# hsa_stm32_board.net
KiCad netlist of a schematic drawn in EAGLE
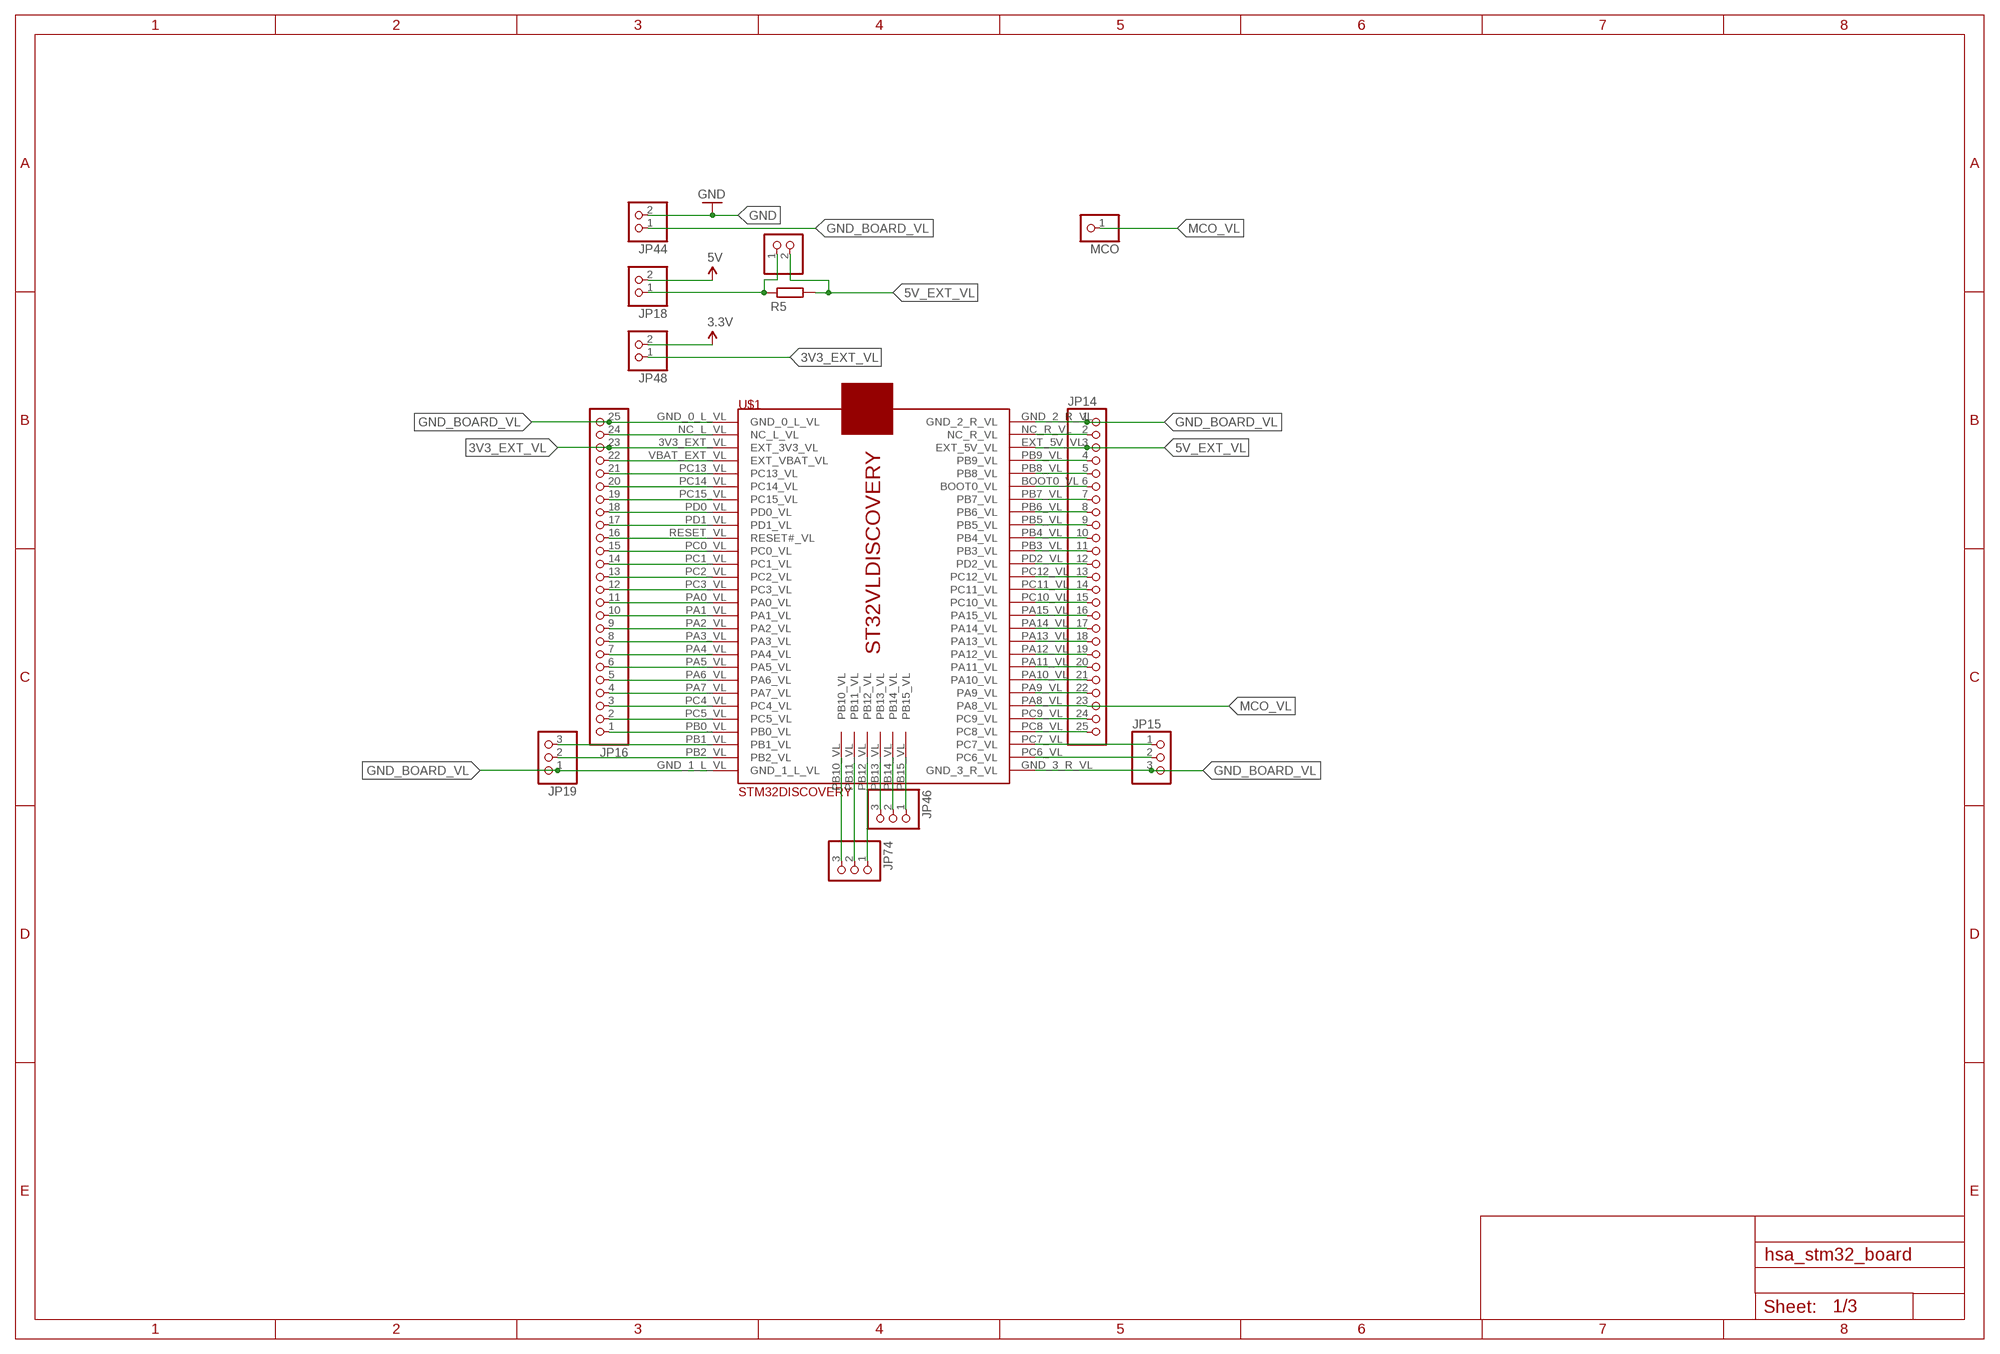
[diagram p0: schematic, sheet 1]
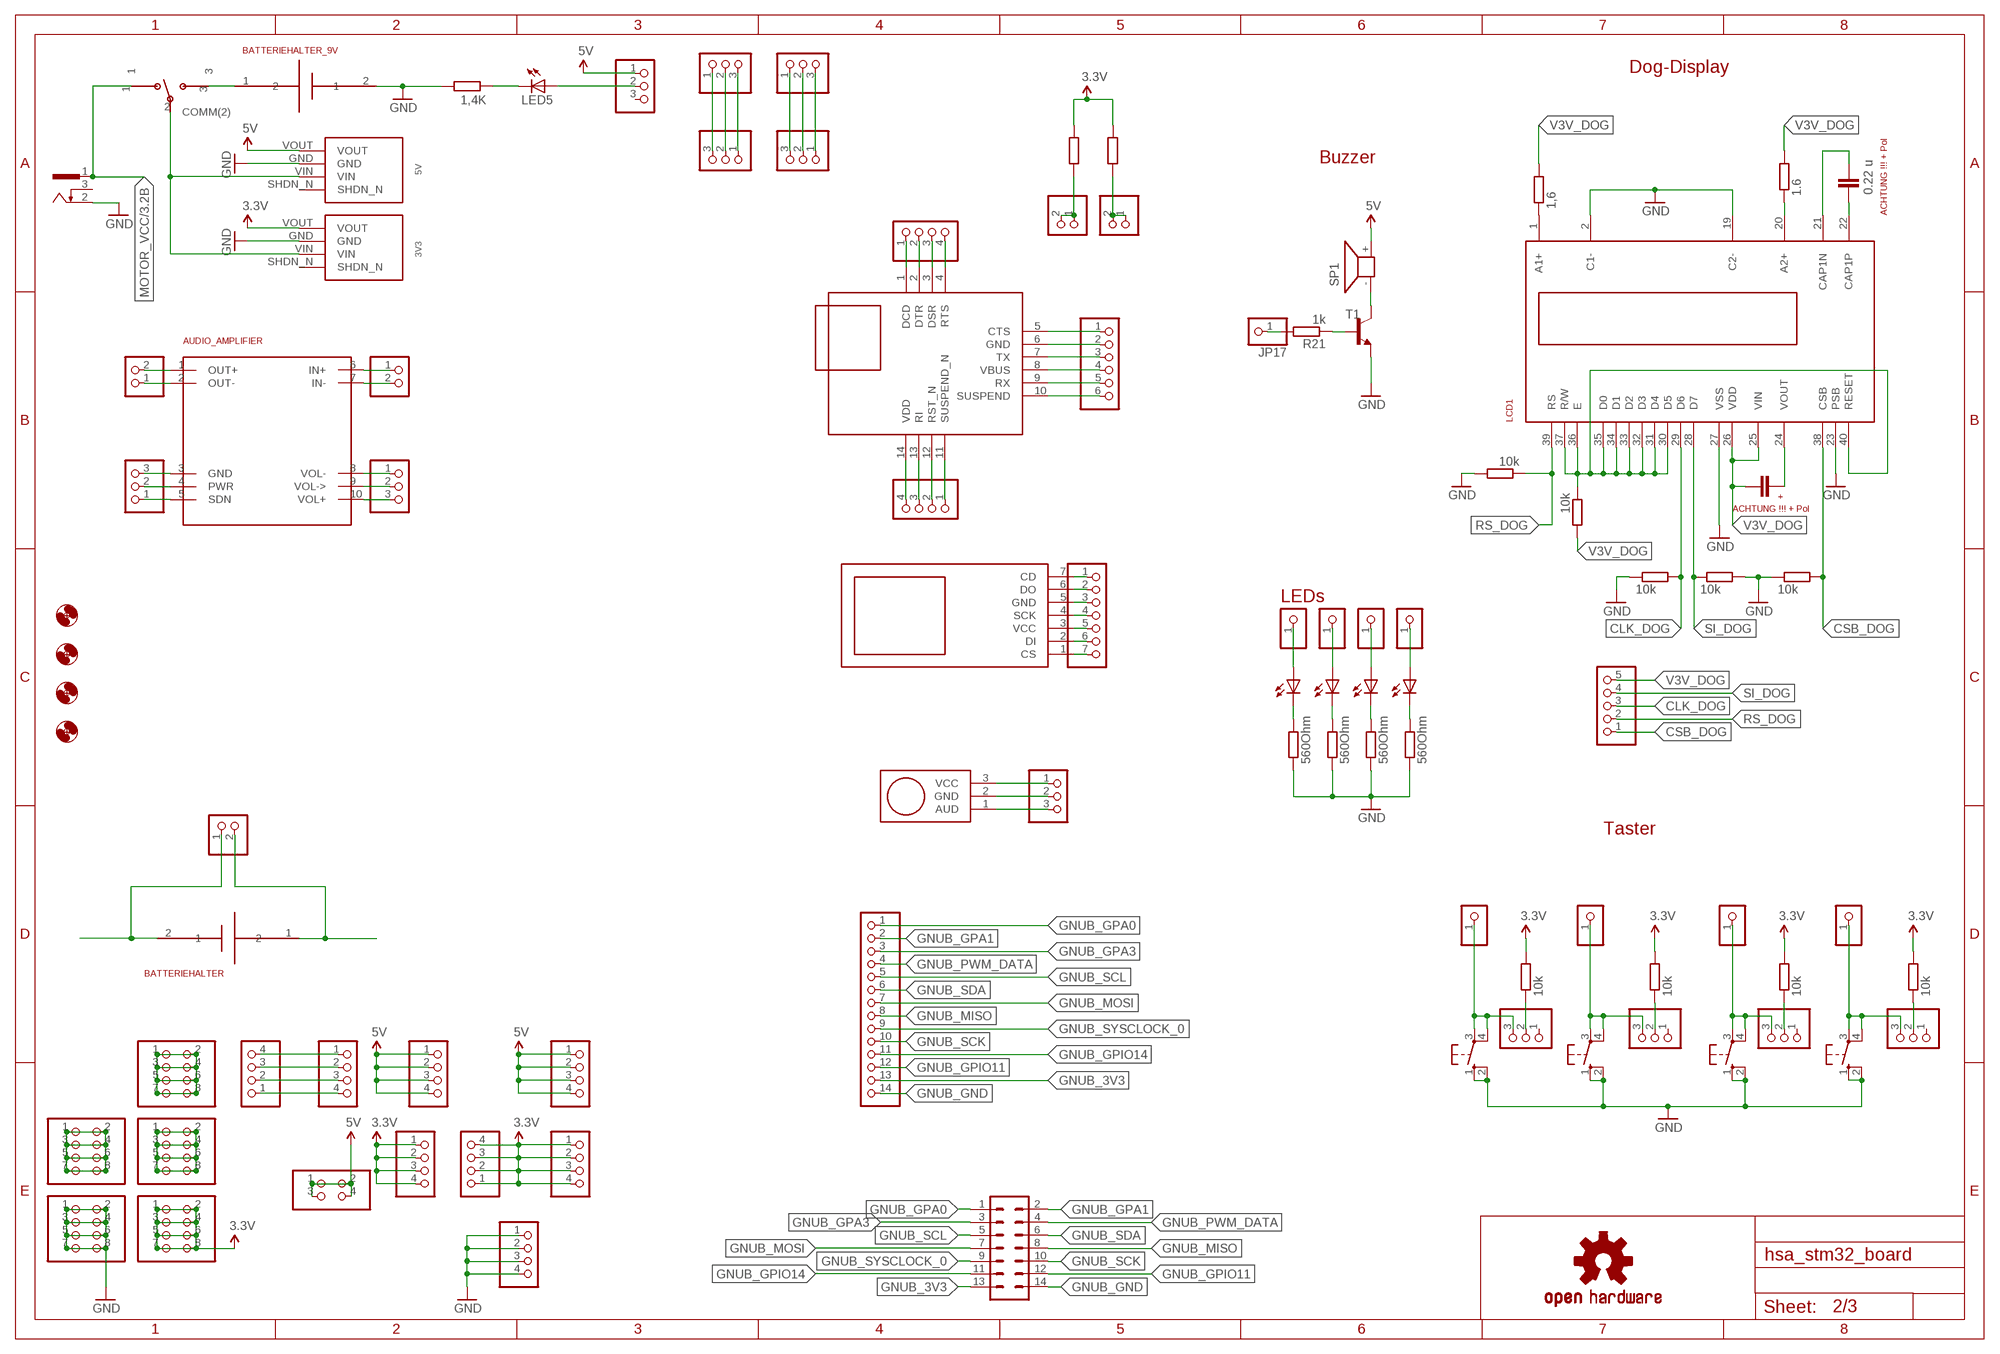
[diagram p1: schematic, sheet 2]
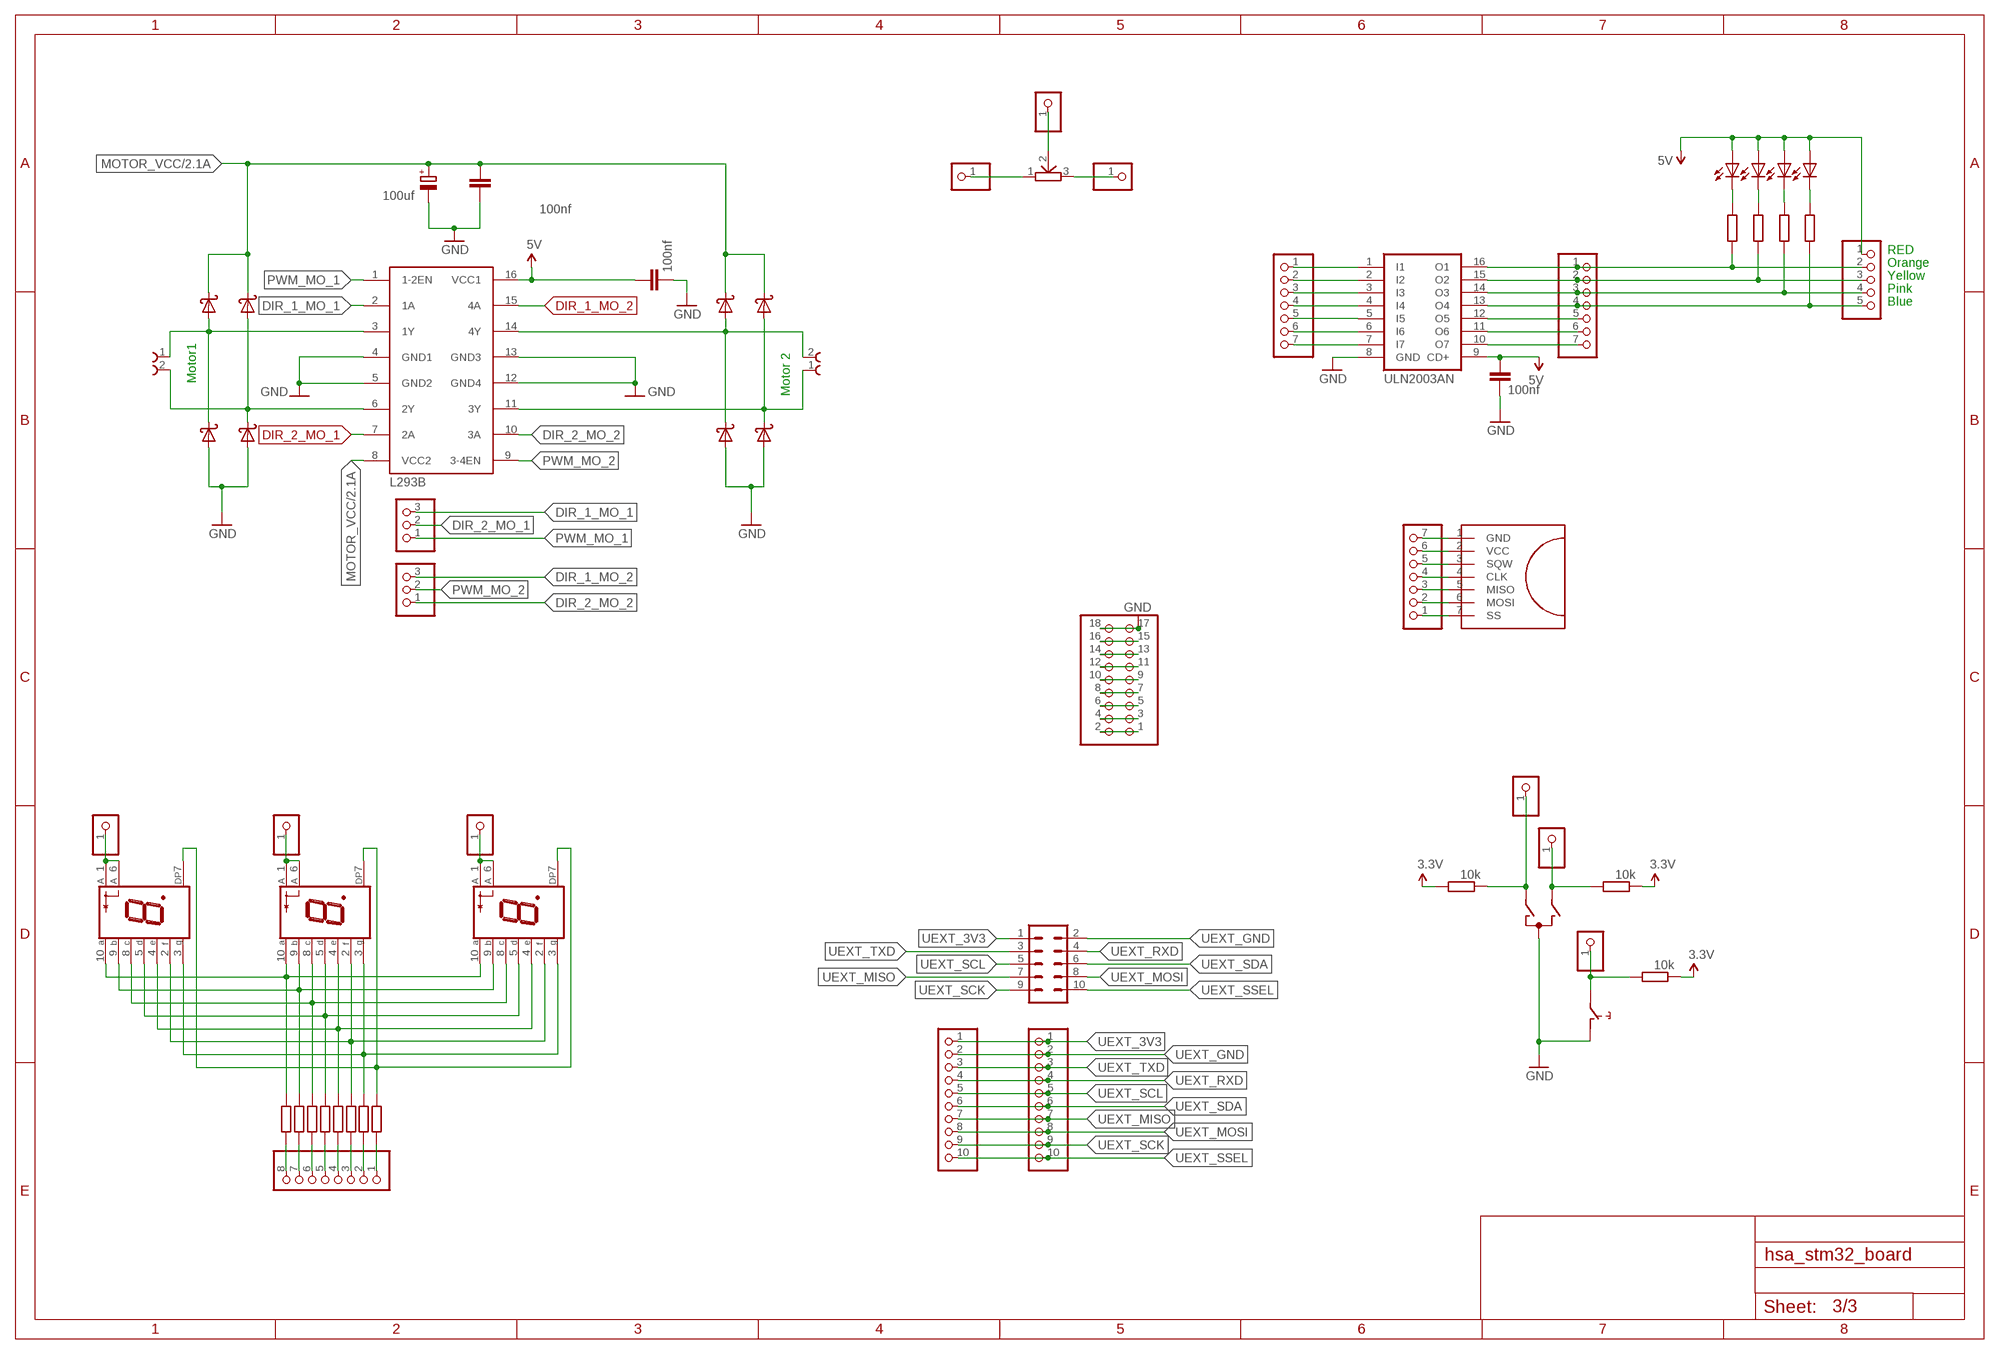
[diagram p2: schematic, sheet 3]

(export (version "E")
  (design (tool "Eeschema 10.0.6"))
  (components
    (comp (ref "JP14")
      (value "PINHD-1X25")
      (footprint "eagle-import:1X25")
      (libsource (lib "eagle-import") (part "PINHD-1X25"))
    )
    (comp (ref "JP15")
      (value "PINHD-1X3")
      (footprint "eagle-import:1X03")
      (libsource (lib "eagle-import") (part "PINHD-1X3"))
    )
    (comp (ref "JP16")
      (value "PINHD-1X25")
      (footprint "eagle-import:1X25")
      (libsource (lib "eagle-import") (part "PINHD-1X25"))
    )
    (comp (ref "JP18")
      (value "PINHD-1X2/90")
      (footprint "eagle-import:1X02_90")
      (libsource (lib "eagle-import") (part "PINHD-1X2/90"))
    )
    (comp (ref "JP19")
      (value "PINHD-1X3")
      (footprint "eagle-import:1X03")
      (libsource (lib "eagle-import") (part "PINHD-1X3"))
    )
    (comp (ref "JP44")
      (value "PINHD-1X2/90")
      (footprint "eagle-import:1X02_90")
      (libsource (lib "eagle-import") (part "PINHD-1X2/90"))
    )
    (comp (ref "JP46")
      (value "PINHD-1X3")
      (footprint "eagle-import:1X03")
      (libsource (lib "eagle-import") (part "PINHD-1X3"))
    )
    (comp (ref "JP48")
      (value "PINHD-1X2/90")
      (footprint "eagle-import:1X02_90")
      (libsource (lib "eagle-import") (part "PINHD-1X2/90"))
    )
    (comp (ref "JP74")
      (value "PINHD-1X3")
      (footprint "eagle-import:1X03")
      (libsource (lib "eagle-import") (part "PINHD-1X3"))
    )
    (comp (ref "JP75")
      (value "PINHD-1X2/90")
      (footprint "eagle-import:1X02_90")
      (libsource (lib "eagle-import") (part "PINHD-1X2/90"))
    )
    (comp (ref "MCO")
      (value "PINHD-1X1")
      (footprint "eagle-import:1X01")
      (libsource (lib "eagle-import") (part "PINHD-1X1"))
    )
    (comp (ref "R5")
      (value "R-EU_0207/10")
      (footprint "eagle-import:0207_10")
      (libsource (lib "eagle-import") (part "R-EU_0207/10"))
    )
    (comp (ref "U$1")
      (value "STM32DISCOVERY")
      (footprint "eagle-import:STM32DISCOVERY")
      (libsource (lib "eagle-import") (part "STM32DISCOVERY"))
    )
    (comp (ref "3V3")
      (value "VOLTAGE_REGULATOR")
      (footprint "eagle-import:VOL_REG")
      (libsource (lib "eagle-import") (part "VOLTAGE_REGULATOR"))
    )
    (comp (ref "5V")
      (value "VOLTAGE_REGULATOR")
      (footprint "eagle-import:VOL_REG")
      (libsource (lib "eagle-import") (part "VOLTAGE_REGULATOR"))
    )
    (comp (ref "C2")
      (value "0.22 u")
      (footprint "eagle-import:C025-040X050")
      (libsource (lib "eagle-import") (part "C-EU025-040X050"))
    )
    (comp (ref "C3")
      (value "1 u")
      (footprint "eagle-import:C025-040X050")
      (libsource (lib "eagle-import") (part "C-EU025-040X050"))
    )
    (comp (ref "H1")
      (value "MOUNT-HOLE2.8")
      (footprint "eagle-import:2,8")
      (libsource (lib "eagle-import") (part "MOUNT-HOLE2.8"))
    )
    (comp (ref "H2")
      (value "MOUNT-HOLE2.8")
      (footprint "eagle-import:2,8")
      (libsource (lib "eagle-import") (part "MOUNT-HOLE2.8"))
    )
    (comp (ref "H3")
      (value "MOUNT-HOLE2.8")
      (footprint "eagle-import:2,8")
      (libsource (lib "eagle-import") (part "MOUNT-HOLE2.8"))
    )
    (comp (ref "H4")
      (value "MOUNT-HOLE2.8")
      (footprint "eagle-import:2,8")
      (libsource (lib "eagle-import") (part "MOUNT-HOLE2.8"))
    )
    (comp (ref "JP1")
      (value "PINHD-1X5")
      (footprint "eagle-import:1X05")
      (libsource (lib "eagle-import") (part "PINHD-1X5"))
    )
    (comp (ref "JP4")
      (value "PINHD-1X3")
      (footprint "eagle-import:1X03")
      (libsource (lib "eagle-import") (part "PINHD-1X3"))
    )
    (comp (ref "JP5")
      (value "PINHD-1X1")
      (footprint "eagle-import:1X01")
      (libsource (lib "eagle-import") (part "PINHD-1X1"))
    )
    (comp (ref "JP6")
      (value "PINHD-1X1")
      (footprint "eagle-import:1X01")
      (libsource (lib "eagle-import") (part "PINHD-1X1"))
    )
    (comp (ref "JP7")
      (value "PINHD-1X1")
      (footprint "eagle-import:1X01")
      (libsource (lib "eagle-import") (part "PINHD-1X1"))
    )
    (comp (ref "JP8")
      (value "PINHD-1X1")
      (footprint "eagle-import:1X01")
      (libsource (lib "eagle-import") (part "PINHD-1X1"))
    )
    (comp (ref "JP9")
      (value "PINHD-1X1")
      (footprint "eagle-import:1X01")
      (libsource (lib "eagle-import") (part "PINHD-1X1"))
    )
    (comp (ref "JP10")
      (value "PINHD-1X1")
      (footprint "eagle-import:1X01")
      (libsource (lib "eagle-import") (part "PINHD-1X1"))
    )
    (comp (ref "JP11")
      (value "PINHD-1X1")
      (footprint "eagle-import:1X01")
      (libsource (lib "eagle-import") (part "PINHD-1X1"))
    )
    (comp (ref "JP12")
      (value "PINHD-1X1")
      (footprint "eagle-import:1X01")
      (libsource (lib "eagle-import") (part "PINHD-1X1"))
    )
    (comp (ref "JP17")
      (value "PINHD-1X1")
      (footprint "eagle-import:1X01")
      (libsource (lib "eagle-import") (part "PINHD-1X1"))
    )
    (comp (ref "JP24")
      (value "PINHD-1X4")
      (footprint "eagle-import:1X04")
      (libsource (lib "eagle-import") (part "PINHD-1X4"))
    )
    (comp (ref "JP27")
      (value "PINHD-1X4/90")
      (footprint "eagle-import:1X04_90")
      (libsource (lib "eagle-import") (part "PINHD-1X4/90"))
    )
    (comp (ref "JP28")
      (value "PINHD-1X4")
      (footprint "eagle-import:1X04")
      (libsource (lib "eagle-import") (part "PINHD-1X4"))
    )
    (comp (ref "JP29")
      (value "PINHD-1X4")
      (footprint "eagle-import:1X04")
      (libsource (lib "eagle-import") (part "PINHD-1X4"))
    )
    (comp (ref "JP30")
      (value "PINHD-1X3")
      (footprint "eagle-import:1X03")
      (libsource (lib "eagle-import") (part "PINHD-1X3"))
    )
    (comp (ref "JP31")
      (value "PINHD-1X2")
      (footprint "eagle-import:1X02")
      (libsource (lib "eagle-import") (part "PINHD-1X2"))
    )
    (comp (ref "JP32")
      (value "PINHD-1X2")
      (footprint "eagle-import:1X02")
      (libsource (lib "eagle-import") (part "PINHD-1X2"))
    )
    (comp (ref "JP33")
      (value "PINHD-1X3")
      (footprint "eagle-import:1X03")
      (libsource (lib "eagle-import") (part "PINHD-1X3"))
    )
    (comp (ref "JP34")
      (value "PINHD-1X3")
      (footprint "eagle-import:1X03")
      (libsource (lib "eagle-import") (part "PINHD-1X3"))
    )
    (comp (ref "JP36")
      (value "PINHD-1X4")
      (footprint "eagle-import:1X04")
      (libsource (lib "eagle-import") (part "PINHD-1X4"))
    )
    (comp (ref "JP37")
      (value "PINHD-1X4")
      (footprint "eagle-import:1X04")
      (libsource (lib "eagle-import") (part "PINHD-1X4"))
    )
    (comp (ref "JP38")
      (value "PINHD-1X6")
      (footprint "eagle-import:1X06")
      (libsource (lib "eagle-import") (part "PINHD-1X6"))
    )
    (comp (ref "JP39")
      (value "PINHD-1X7")
      (footprint "eagle-import:1X07")
      (libsource (lib "eagle-import") (part "PINHD-1X7"))
    )
    (comp (ref "JP40")
      (value "PINHD-1X4")
      (footprint "eagle-import:1X04")
      (libsource (lib "eagle-import") (part "PINHD-1X4"))
    )
    (comp (ref "JP41")
      (value "PINHD-1X4")
      (footprint "eagle-import:1X04")
      (libsource (lib "eagle-import") (part "PINHD-1X4"))
    )
    (comp (ref "JP42")
      (value "PINHD-1X4")
      (footprint "eagle-import:1X04")
      (libsource (lib "eagle-import") (part "PINHD-1X4"))
    )
    (comp (ref "JP43")
      (value "PINHD-1X2")
      (footprint "eagle-import:1X02")
      (libsource (lib "eagle-import") (part "PINHD-1X2"))
    )
    (comp (ref "JP45")
      (value "PINHD-2X4")
      (footprint "eagle-import:2X04")
      (libsource (lib "eagle-import") (part "PINHD-2X4"))
    )
    (comp (ref "JP47")
      (value "PINHD-1X4")
      (footprint "eagle-import:1X04")
      (libsource (lib "eagle-import") (part "PINHD-1X4"))
    )
    (comp (ref "JP49")
      (value "PINHD-1X3/90")
      (footprint "eagle-import:1X03_90")
      (libsource (lib "eagle-import") (part "PINHD-1X3/90"))
    )
    (comp (ref "JP50")
      (value "PINHD-1X3")
      (footprint "eagle-import:1X03")
      (libsource (lib "eagle-import") (part "PINHD-1X3"))
    )
    (comp (ref "JP51")
      (value "PINHD-1X3/90")
      (footprint "eagle-import:1X03_90")
      (libsource (lib "eagle-import") (part "PINHD-1X3/90"))
    )
    (comp (ref "JP52")
      (value "PINHD-1X3")
      (footprint "eagle-import:1X03")
      (libsource (lib "eagle-import") (part "PINHD-1X3"))
    )
    (comp (ref "JP59")
      (value "PINHD-1X3")
      (footprint "eagle-import:1X03")
      (libsource (lib "eagle-import") (part "PINHD-1X3"))
    )
    (comp (ref "JP60")
      (value "PINHD-1X3")
      (footprint "eagle-import:1X03")
      (libsource (lib "eagle-import") (part "PINHD-1X3"))
    )
    (comp (ref "JP61")
      (value "PINHD-1X3")
      (footprint "eagle-import:1X03")
      (libsource (lib "eagle-import") (part "PINHD-1X3"))
    )
    (comp (ref "JP62")
      (value "PINHD-1X3")
      (footprint "eagle-import:1X03")
      (libsource (lib "eagle-import") (part "PINHD-1X3"))
    )
    (comp (ref "JP64")
      (value "PINHD-1X14")
      (footprint "eagle-import:1X14")
      (libsource (lib "eagle-import") (part "PINHD-1X14"))
    )
    (comp (ref "JP65")
      (value "PINHD-1X2")
      (footprint "eagle-import:1X02")
      (libsource (lib "eagle-import") (part "PINHD-1X2"))
    )
    (comp (ref "JP66")
      (value "PINHD-1X2")
      (footprint "eagle-import:1X02")
      (libsource (lib "eagle-import") (part "PINHD-1X2"))
    )
    (comp (ref "JP67")
      (value "PINHD-2X4")
      (footprint "eagle-import:2X04")
      (libsource (lib "eagle-import") (part "PINHD-2X4"))
    )
    (comp (ref "JP68")
      (value "PINHD-2X4")
      (footprint "eagle-import:2X04")
      (libsource (lib "eagle-import") (part "PINHD-2X4"))
    )
    (comp (ref "JP69")
      (value "PINHD-2X4")
      (footprint "eagle-import:2X04")
      (libsource (lib "eagle-import") (part "PINHD-2X4"))
    )
    (comp (ref "JP70")
      (value "PINHD-2X4")
      (footprint "eagle-import:2X04")
      (libsource (lib "eagle-import") (part "PINHD-2X4"))
    )
    (comp (ref "JP71")
      (value "PINHD-2X2")
      (footprint "eagle-import:2X02")
      (libsource (lib "eagle-import") (part "PINHD-2X2"))
    )
    (comp (ref "LCD1")
      (value "ZEITERFASSUNG_-OPTO_DOGM")
      (footprint "eagle-import:ZEITERFASSUNG_-OPTO_DOGM")
      (libsource (lib "eagle-import") (part "ZEITERFASSUNG_-OPTO_DOGM"))
    )
    (comp (ref "LED1")
      (value "LED5MM")
      (footprint "eagle-import:LED5MM")
      (libsource (lib "eagle-import") (part "LED5MM"))
    )
    (comp (ref "LED2")
      (value "LED5MM")
      (footprint "eagle-import:LED5MM")
      (libsource (lib "eagle-import") (part "LED5MM"))
    )
    (comp (ref "LED3")
      (value "LED5MM")
      (footprint "eagle-import:LED5MM")
      (libsource (lib "eagle-import") (part "LED5MM"))
    )
    (comp (ref "LED4")
      (value "LED5MM")
      (footprint "eagle-import:LED5MM")
      (libsource (lib "eagle-import") (part "LED5MM"))
    )
    (comp (ref "LED5")
      (value "LED5MM")
      (footprint "eagle-import:LED5MM")
      (libsource (lib "eagle-import") (part "LED5MM"))
    )
    (comp (ref "LOGO1")
      (value "OSHW-LOGOL")
      (footprint "eagle-import:OSHW-LOGO-L")
      (libsource (lib "eagle-import") (part "OSHW-LOGOL"))
    )
    (comp (ref "R1")
      (value "560Ohm")
      (footprint "eagle-import:0207_10")
      (libsource (lib "eagle-import") (part "R-EU_0207/10"))
    )
    (comp (ref "R2")
      (value "560Ohm")
      (footprint "eagle-import:0207_10")
      (libsource (lib "eagle-import") (part "R-EU_0207/10"))
    )
    (comp (ref "R3")
      (value "560Ohm")
      (footprint "eagle-import:0207_10")
      (libsource (lib "eagle-import") (part "R-EU_0207/10"))
    )
    (comp (ref "R4")
      (value "560Ohm")
      (footprint "eagle-import:0207_10")
      (libsource (lib "eagle-import") (part "R-EU_0207/10"))
    )
    (comp (ref "R6")
      (value "1,4K")
      (footprint "eagle-import:0207_10")
      (libsource (lib "eagle-import") (part "R-EU_0207/10"))
    )
    (comp (ref "R7")
      (value "1.6")
      (footprint "eagle-import:0207_10")
      (libsource (lib "eagle-import") (part "R-EU_0207/10"))
    )
    (comp (ref "R8")
      (value "1,6")
      (footprint "eagle-import:0207_10")
      (libsource (lib "eagle-import") (part "R-EU_0207/10"))
    )
    (comp (ref "R9")
      (value "10k")
      (footprint "eagle-import:0207_10")
      (libsource (lib "eagle-import") (part "R-EU_0207/10"))
    )
    (comp (ref "R10")
      (value "10k")
      (footprint "eagle-import:0207_10")
      (libsource (lib "eagle-import") (part "R-EU_0207/10"))
    )
    (comp (ref "R11")
      (value "10k")
      (footprint "eagle-import:0207_10")
      (libsource (lib "eagle-import") (part "R-EU_0207/10"))
    )
    (comp (ref "R12")
      (value "10k")
      (footprint "eagle-import:0207_10")
      (libsource (lib "eagle-import") (part "R-EU_0207/10"))
    )
    (comp (ref "R13")
      (value "10k")
      (footprint "eagle-import:0207_10")
      (libsource (lib "eagle-import") (part "R-EU_0207/10"))
    )
    (comp (ref "R14")
      (value "10k")
      (footprint "eagle-import:0207_10")
      (libsource (lib "eagle-import") (part "R-EU_0207/10"))
    )
    (comp (ref "R15")
      (value "10k")
      (footprint "eagle-import:0207_10")
      (libsource (lib "eagle-import") (part "R-EU_0207/10"))
    )
    (comp (ref "R16")
      (value "10k")
      (footprint "eagle-import:0207_10")
      (libsource (lib "eagle-import") (part "R-EU_0207/10"))
    )
    (comp (ref "R17")
      (value "10k")
      (footprint "eagle-import:0207_10")
      (libsource (lib "eagle-import") (part "R-EU_0207/10"))
    )
    (comp (ref "R21")
      (value "1k")
      (footprint "eagle-import:0207_10")
      (libsource (lib "eagle-import") (part "R-EU_0207/10"))
    )
    (comp (ref "R22")
      (value "R-EU_0207/10")
      (footprint "eagle-import:0207_10")
      (libsource (lib "eagle-import") (part "R-EU_0207/10"))
    )
    (comp (ref "R23")
      (value "R-EU_0207/10")
      (footprint "eagle-import:0207_10")
      (libsource (lib "eagle-import") (part "R-EU_0207/10"))
    )
    (comp (ref "S1")
      (value "CPU-K_MODULE_REV3.0_SWITCH-OMRON_10-XX")
      (footprint "eagle-import:CPU-K_MODULE_REV3.0_SWITCH-OMRON_B3F-10XX")
      (libsource (lib "eagle-import") (part "CPU-K_MODULE_REV3.0_SWITCH-OMRON_10-XX"))
    )
    (comp (ref "S2")
      (value "CPU-K_MODULE_REV3.0_SWITCH-OMRON_10-XX")
      (footprint "eagle-import:CPU-K_MODULE_REV3.0_SWITCH-OMRON_B3F-10XX")
      (libsource (lib "eagle-import") (part "CPU-K_MODULE_REV3.0_SWITCH-OMRON_10-XX"))
    )
    (comp (ref "S3")
      (value "CPU-K_MODULE_REV3.0_SWITCH-OMRON_10-XX")
      (footprint "eagle-import:CPU-K_MODULE_REV3.0_SWITCH-OMRON_B3F-10XX")
      (libsource (lib "eagle-import") (part "CPU-K_MODULE_REV3.0_SWITCH-OMRON_10-XX"))
    )
    (comp (ref "S4")
      (value "CPU-K_MODULE_REV3.0_SWITCH-OMRON_10-XX")
      (footprint "eagle-import:CPU-K_MODULE_REV3.0_SWITCH-OMRON_B3F-10XX")
      (libsource (lib "eagle-import") (part "CPU-K_MODULE_REV3.0_SWITCH-OMRON_10-XX"))
    )
    (comp (ref "SP1")
      (value "BUZZER_F/PMX04")
      (footprint "eagle-import:BUZZER_F_PMX04A")
      (libsource (lib "eagle-import") (part "BUZZER_F/PMX04"))
    )
    (comp (ref "SV3")
      (value "ML14")
      (footprint "eagle-import:ML14")
      (libsource (lib "eagle-import") (part "ML14"))
    )
    (comp (ref "T1")
      (value "TRANSISTOR_BC337")
      (footprint "eagle-import:TRANSISTOR_TO92")
      (libsource (lib "eagle-import") (part "TRANSISTOR_BC337"))
    )
    (comp (ref "U$2")
      (value "USB_TO_SERIAL_ADAPTER")
      (footprint "eagle-import:USB_TO_SERIAL")
      (libsource (lib "eagle-import") (part "USB_TO_SERIAL_ADAPTER"))
    )
    (comp (ref "U$4")
      (value "KIPPSCHALTER(EIN,AUS,EIN)")
      (footprint "eagle-import:KIPPSCHALTER")
      (libsource (lib "eagle-import") (part "KIPPSCHALTER(EIN,AUS,EIN)"))
    )
    (comp (ref "U$5")
      (value "MIC")
      (footprint "eagle-import:MIC")
      (libsource (lib "eagle-import") (part "MIC"))
    )
    (comp (ref "U$6")
      (value "BATTERIEHALTER")
      (footprint "eagle-import:BH_KZH_20")
      (libsource (lib "eagle-import") (part "BATTERIEHALTER"))
    )
    (comp (ref "U$7")
      (value "BATTERIEHALTER_9V")
      (footprint "eagle-import:BATTERIEHALTER_9V")
      (libsource (lib "eagle-import") (part "BATTERIEHALTER_9V"))
    )
    (comp (ref "U$9")
      (value "AUDIO_AMPLIFIER")
      (footprint "eagle-import:AUDIO_AMPLIFIER")
      (libsource (lib "eagle-import") (part "AUDIO_AMPLIFIER"))
    )
    (comp (ref "U$12")
      (value "MICRO_SD_HALTER")
      (footprint "eagle-import:MIKRO_SD_HALTER")
      (libsource (lib "eagle-import") (part "MICRO_SD_HALTER"))
    )
    (comp (ref "X1")
      (value "733980-62")
      (footprint "eagle-import:733980-62")
      (libsource (lib "eagle-import") (part "73398?0-62"))
    )
    (comp (ref "C4")
      (value "100nf")
      (footprint "eagle-import:RCL_C025-040X050")
      (libsource (lib "eagle-import") (part "RCL_C-EU025-040X050"))
    )
    (comp (ref "C5")
      (value "100nf")
      (footprint "eagle-import:RCL_C025-040X050")
      (libsource (lib "eagle-import") (part "RCL_C-EU025-040X050"))
    )
    (comp (ref "C6")
      (value "100nf")
      (footprint "eagle-import:RCL_C025-040X050")
      (libsource (lib "eagle-import") (part "RCL_C-EU025-040X050"))
    )
    (comp (ref "C7")
      (value "100uf")
      (footprint "eagle-import:RCL_E2,5-6")
      (libsource (lib "eagle-import") (part "RCL_CPOL-EUE2.5-6"))
    )
    (comp (ref "D1")
      (value "1N5819")
      (footprint "eagle-import:DO41-10")
      (libsource (lib "eagle-import") (part "1N5819"))
    )
    (comp (ref "D2")
      (value "1N5819")
      (footprint "eagle-import:DO41-10")
      (libsource (lib "eagle-import") (part "1N5819"))
    )
    (comp (ref "D3")
      (value "1N5819")
      (footprint "eagle-import:DO41-10")
      (libsource (lib "eagle-import") (part "1N5819"))
    )
    (comp (ref "D4")
      (value "1N5819")
      (footprint "eagle-import:DO41-10")
      (libsource (lib "eagle-import") (part "1N5819"))
    )
    (comp (ref "D5")
      (value "1N5819")
      (footprint "eagle-import:DO41-10")
      (libsource (lib "eagle-import") (part "1N5819"))
    )
    (comp (ref "D6")
      (value "1N5819")
      (footprint "eagle-import:DO41-10")
      (libsource (lib "eagle-import") (part "1N5819"))
    )
    (comp (ref "D7")
      (value "1N5819")
      (footprint "eagle-import:DO41-10")
      (libsource (lib "eagle-import") (part "1N5819"))
    )
    (comp (ref "D8")
      (value "1N5819")
      (footprint "eagle-import:DO41-10")
      (libsource (lib "eagle-import") (part "1N5819"))
    )
    (comp (ref "IC1")
      (value "ULN2003AN")
      (footprint "eagle-import:DIL16")
      (libsource (lib "eagle-import") (part "ULN2003AN"))
    )
    (comp (ref "IC2")
      (value "L293D")
      (footprint "eagle-import:DIL16")
      (libsource (lib "eagle-import") (part "L293D"))
    )
    (comp (ref "JP2")
      (value "PINHD-1X1")
      (footprint "eagle-import:1X01")
      (libsource (lib "eagle-import") (part "PINHD-1X1"))
    )
    (comp (ref "JP3")
      (value "PINHD-1X1")
      (footprint "eagle-import:1X01")
      (libsource (lib "eagle-import") (part "PINHD-1X1"))
    )
    (comp (ref "JP13")
      (value "PINHD-1X1")
      (footprint "eagle-import:1X01")
      (libsource (lib "eagle-import") (part "PINHD-1X1"))
    )
    (comp (ref "JP20")
      (value "PINHD-1X10")
      (footprint "eagle-import:1X10")
      (libsource (lib "eagle-import") (part "PINHD-1X10"))
    )
    (comp (ref "JP21")
      (value "PINHD-1X7")
      (footprint "eagle-import:1X07")
      (libsource (lib "eagle-import") (part "PINHD-1X7"))
    )
    (comp (ref "JP22")
      (value "PINHD-1X8")
      (footprint "eagle-import:1X08")
      (libsource (lib "eagle-import") (part "PINHD-1X8"))
    )
    (comp (ref "JP23")
      (value "PINHD-1X1")
      (footprint "eagle-import:1X01")
      (libsource (lib "eagle-import") (part "PINHD-1X1"))
    )
    (comp (ref "JP25")
      (value "PINHD-1X5/90")
      (footprint "eagle-import:1X05_90")
      (libsource (lib "eagle-import") (part "PINHD-1X5/90"))
    )
    (comp (ref "JP26")
      (value "PINHD-1X7")
      (footprint "eagle-import:1X07")
      (libsource (lib "eagle-import") (part "PINHD-1X7"))
    )
    (comp (ref "JP35")
      (value "PINHD-1X7")
      (footprint "eagle-import:1X07")
      (libsource (lib "eagle-import") (part "PINHD-1X7"))
    )
    (comp (ref "JP53")
      (value "PINHD-1X1")
      (footprint "eagle-import:1X01")
      (libsource (lib "eagle-import") (part "PINHD-1X1"))
    )
    (comp (ref "JP54")
      (value "PINHD-1X1")
      (footprint "eagle-import:1X01")
      (libsource (lib "eagle-import") (part "PINHD-1X1"))
    )
    (comp (ref "JP55")
      (value "PINHD-1X1")
      (footprint "eagle-import:1X01")
      (libsource (lib "eagle-import") (part "PINHD-1X1"))
    )
    (comp (ref "JP56")
      (value "PINHD-2X9")
      (footprint "eagle-import:2X09")
      (libsource (lib "eagle-import") (part "PINHD-2X9"))
    )
    (comp (ref "JP57")
      (value "PINHD-1X3")
      (footprint "eagle-import:1X03")
      (libsource (lib "eagle-import") (part "PINHD-1X3"))
    )
    (comp (ref "JP58")
      (value "PINHD-1X3")
      (footprint "eagle-import:1X03")
      (libsource (lib "eagle-import") (part "PINHD-1X3"))
    )
    (comp (ref "JP63")
      (value "PINHD-1X10")
      (footprint "eagle-import:1X10")
      (libsource (lib "eagle-import") (part "PINHD-1X10"))
    )
    (comp (ref "JP72")
      (value "PINHD-1X1")
      (footprint "eagle-import:1X01")
      (libsource (lib "eagle-import") (part "PINHD-1X1"))
    )
    (comp (ref "JP73")
      (value "PINHD-1X1")
      (footprint "eagle-import:1X01")
      (libsource (lib "eagle-import") (part "PINHD-1X1"))
    )
    (comp (ref "K1")
      (value "691210910002")
      (footprint "eagle-import:691210910002")
      (libsource (lib "eagle-import") (part "691210910002"))
    )
    (comp (ref "K2")
      (value "691210910002")
      (footprint "eagle-import:691210910002")
      (libsource (lib "eagle-import") (part "691210910002"))
    )
    (comp (ref "LED6")
      (value "LA-401MD")
      (footprint "eagle-import:LA-401")
      (libsource (lib "eagle-import") (part "LA-401DM"))
    )
    (comp (ref "LED7")
      (value "LA-401MD")
      (footprint "eagle-import:LA-401")
      (libsource (lib "eagle-import") (part "LA-401DM"))
    )
    (comp (ref "LED8")
      (value "LA-401MD")
      (footprint "eagle-import:LA-401")
      (libsource (lib "eagle-import") (part "LA-401DM"))
    )
    (comp (ref "LED9")
      (value "LED3MM")
      (footprint "eagle-import:LED3MM")
      (libsource (lib "eagle-import") (part "LED3MM"))
    )
    (comp (ref "LED10")
      (value "LED3MM")
      (footprint "eagle-import:LED3MM")
      (libsource (lib "eagle-import") (part "LED3MM"))
    )
    (comp (ref "LED11")
      (value "LED3MM")
      (footprint "eagle-import:LED3MM")
      (libsource (lib "eagle-import") (part "LED3MM"))
    )
    (comp (ref "LED12")
      (value "LED3MM")
      (footprint "eagle-import:LED3MM")
      (libsource (lib "eagle-import") (part "LED3MM"))
    )
    (comp (ref "R18")
      (value "10k")
      (footprint "eagle-import:0207_10")
      (libsource (lib "eagle-import") (part "R-EU_0207/10"))
    )
    (comp (ref "R19")
      (value "10k")
      (footprint "eagle-import:0207_10")
      (libsource (lib "eagle-import") (part "R-EU_0207/10"))
    )
    (comp (ref "R20")
      (value "10k")
      (footprint "eagle-import:0207_10")
      (libsource (lib "eagle-import") (part "R-EU_0207/10"))
    )
    (comp (ref "R24")
      (value "R-EU_0207/10")
      (footprint "eagle-import:0207_10")
      (libsource (lib "eagle-import") (part "R-EU_0207/10"))
    )
    (comp (ref "R25")
      (value "R-EU_0207/10")
      (footprint "eagle-import:0207_10")
      (libsource (lib "eagle-import") (part "R-EU_0207/10"))
    )
    (comp (ref "R26")
      (value "R-EU_0207/10")
      (footprint "eagle-import:0207_10")
      (libsource (lib "eagle-import") (part "R-EU_0207/10"))
    )
    (comp (ref "R27")
      (value "R-EU_0207/10")
      (footprint "eagle-import:0207_10")
      (libsource (lib "eagle-import") (part "R-EU_0207/10"))
    )
    (comp (ref "R28")
      (value "R-EU_0207/10")
      (footprint "eagle-import:0207_10")
      (libsource (lib "eagle-import") (part "R-EU_0207/10"))
    )
    (comp (ref "R29")
      (value "R-EU_0207/10")
      (footprint "eagle-import:0207_10")
      (libsource (lib "eagle-import") (part "R-EU_0207/10"))
    )
    (comp (ref "R30")
      (value "R-EU_0207/10")
      (footprint "eagle-import:0207_10")
      (libsource (lib "eagle-import") (part "R-EU_0207/10"))
    )
    (comp (ref "R31")
      (value "R-EU_0207/10")
      (footprint "eagle-import:0207_10")
      (libsource (lib "eagle-import") (part "R-EU_0207/10"))
    )
    (comp (ref "R32")
      (value "R-EU_0207/10")
      (footprint "eagle-import:0207_10")
      (libsource (lib "eagle-import") (part "R-EU_0207/10"))
    )
    (comp (ref "R33")
      (value "R-EU_0207/10")
      (footprint "eagle-import:0207_10")
      (libsource (lib "eagle-import") (part "R-EU_0207/10"))
    )
    (comp (ref "R34")
      (value "R-EU_0207/10")
      (footprint "eagle-import:0207_10")
      (libsource (lib "eagle-import") (part "R-EU_0207/10"))
    )
    (comp (ref "R35")
      (value "R-EU_0207/10")
      (footprint "eagle-import:0207_10")
      (libsource (lib "eagle-import") (part "R-EU_0207/10"))
    )
    (comp (ref "SV2")
      (value "CON-HARTING-ML_ML10")
      (footprint "eagle-import:CON-HARTING-ML_ML10")
      (libsource (lib "eagle-import") (part "CON-HARTING-ML_ML10"))
    )
    (comp (ref "SW1")
      (value "EC12E_SW")
      (footprint "eagle-import:ALPS_EC12E_SW")
      (fields (field (name "MPN") "EC12E2424407"))
      (libsource (lib "eagle-import") (part "EC12E_SW"))
    )
    (comp (ref "U$10")
      (value "RTC")
      (footprint "eagle-import:RTC")
      (libsource (lib "eagle-import") (part "RTC"))
    )
    (comp (ref "U$17")
      (value "THUMBWHEEL_POTI")
      (footprint "eagle-import:THUMBWHEEL_POTI")
      (libsource (lib "eagle-import") (part "THUMBWHEEL_POTI"))
    )
  )
  (nets
    (net (code "1") (name "3.3V") (class "Default")
      (node (ref "3V3") (pin "VOUT") (pinfunction "VOUT_VOUT") (pintype "bidirectional"))
      (node (ref "JP29") (pin "1") (pinfunction "1_1") (pintype "passive"))
      (node (ref "JP29") (pin "2") (pinfunction "2_2") (pintype "passive"))
      (node (ref "JP29") (pin "3") (pinfunction "3_3") (pintype "passive"))
      (node (ref "JP29") (pin "4") (pinfunction "4_4") (pintype "passive"))
      (node (ref "JP41") (pin "1") (pinfunction "1_1") (pintype "passive"))
      (node (ref "JP41") (pin "2") (pinfunction "2_2") (pintype "passive"))
      (node (ref "JP41") (pin "3") (pinfunction "3_3") (pintype "passive"))
      (node (ref "JP41") (pin "4") (pinfunction "4_4") (pintype "passive"))
      (node (ref "JP47") (pin "1") (pinfunction "1_1") (pintype "passive"))
      (node (ref "JP47") (pin "2") (pinfunction "2_2") (pintype "passive"))
      (node (ref "JP47") (pin "3") (pinfunction "3_3") (pintype "passive"))
      (node (ref "JP47") (pin "4") (pinfunction "4_4") (pintype "passive"))
      (node (ref "JP48") (pin "2") (pinfunction "2_2") (pintype "passive"))
      (node (ref "JP70") (pin "1") (pinfunction "1_1") (pintype "passive"))
      (node (ref "JP70") (pin "2") (pinfunction "2_2") (pintype "passive"))
      (node (ref "JP70") (pin "3") (pinfunction "3_3") (pintype "passive"))
      (node (ref "JP70") (pin "4") (pinfunction "4_4") (pintype "passive"))
      (node (ref "JP70") (pin "5") (pinfunction "5_5") (pintype "passive"))
      (node (ref "JP70") (pin "6") (pinfunction "6_6") (pintype "passive"))
      (node (ref "JP70") (pin "7") (pinfunction "7_7") (pintype "passive"))
      (node (ref "JP70") (pin "8") (pinfunction "8_8") (pintype "passive"))
      (node (ref "R14") (pin "2") (pinfunction "2_2") (pintype "passive"))
      (node (ref "R15") (pin "2") (pinfunction "2_2") (pintype "passive"))
      (node (ref "R16") (pin "2") (pinfunction "2_2") (pintype "passive"))
      (node (ref "R17") (pin "2") (pinfunction "2_2") (pintype "passive"))
      (node (ref "R18") (pin "1") (pinfunction "1_1") (pintype "passive"))
      (node (ref "R19") (pin "2") (pinfunction "2_2") (pintype "passive"))
      (node (ref "R20") (pin "1") (pinfunction "1_1") (pintype "passive"))
      (node (ref "R22") (pin "2") (pinfunction "2_2") (pintype "passive"))
      (node (ref "R23") (pin "2") (pinfunction "2_2") (pintype "passive"))
    )
    (net (code "2") (name "3V3_EXT_VL") (class "Default")
      (node (ref "JP16") (pin "23") (pinfunction "23_23") (pintype "passive"))
      (node (ref "JP48") (pin "1") (pinfunction "1_1") (pintype "passive"))
      (node (ref "U$1") (pin "3V3_EXT_VL") (pinfunction "EXT_3V3_VL_3V3_EXT_VL") (pintype "bidirectional"))
    )
    (net (code "3") (name "5V") (class "Default")
      (node (ref "5V") (pin "VOUT") (pinfunction "VOUT_VOUT") (pintype "bidirectional"))
      (node (ref "C4") (pin "1") (pinfunction "1_1") (pintype "passive"))
      (node (ref "C6") (pin "1") (pinfunction "1_1") (pintype "passive"))
      (node (ref "IC1") (pin "9") (pinfunction "CD+_9") (pintype "passive"))
      (node (ref "IC2") (pin "16") (pinfunction "VCC1_16") (pintype "power_in"))
      (node (ref "JP18") (pin "2") (pinfunction "2_2") (pintype "passive"))
      (node (ref "JP25") (pin "1") (pinfunction "1_1") (pintype "passive"))
      (node (ref "JP28") (pin "1") (pinfunction "1_1") (pintype "passive"))
      (node (ref "JP28") (pin "2") (pinfunction "2_2") (pintype "passive"))
      (node (ref "JP28") (pin "3") (pinfunction "3_3") (pintype "passive"))
      (node (ref "JP28") (pin "4") (pinfunction "4_4") (pintype "passive"))
      (node (ref "JP4") (pin "1") (pinfunction "1_1") (pintype "passive"))
      (node (ref "JP40") (pin "1") (pinfunction "1_1") (pintype "passive"))
      (node (ref "JP40") (pin "2") (pinfunction "2_2") (pintype "passive"))
      (node (ref "JP40") (pin "3") (pinfunction "3_3") (pintype "passive"))
      (node (ref "JP40") (pin "4") (pinfunction "4_4") (pintype "passive"))
      (node (ref "JP71") (pin "1") (pinfunction "1_1") (pintype "passive"))
      (node (ref "JP71") (pin "2") (pinfunction "2_2") (pintype "passive"))
      (node (ref "JP71") (pin "3") (pinfunction "3_3") (pintype "passive"))
      (node (ref "JP71") (pin "4") (pinfunction "4_4") (pintype "passive"))
      (node (ref "LED10") (pin "A") (pinfunction "A_A") (pintype "passive"))
      (node (ref "LED11") (pin "A") (pinfunction "A_A") (pintype "passive"))
      (node (ref "LED12") (pin "A") (pinfunction "A_A") (pintype "passive"))
      (node (ref "LED9") (pin "A") (pinfunction "A_A") (pintype "passive"))
      (node (ref "SP1") (pin "+") (pinfunction "2_+") (pintype "passive"))
    )
    (net (code "4") (name "5V_EXT_VL") (class "Default")
      (node (ref "JP14") (pin "3") (pinfunction "3_3") (pintype "passive"))
      (node (ref "JP75") (pin "2") (pinfunction "2_2") (pintype "passive"))
      (node (ref "R5") (pin "2") (pinfunction "2_2") (pintype "passive"))
      (node (ref "U$1") (pin "EXT_5V_VL") (pinfunction "EXT_5V_VL_EXT_5V_VL") (pintype "bidirectional"))
    )
    (net (code "5") (name "CLK_DOG") (class "Default")
      (node (ref "JP1") (pin "3") (pinfunction "3_3") (pintype "passive"))
      (node (ref "LCD1") (pin "29") (pinfunction "D6_29") (pintype "bidirectional"))
      (node (ref "R11") (pin "2") (pinfunction "2_2") (pintype "passive"))
    )
    (net (code "6") (name "CSB_DOG") (class "Default")
      (node (ref "JP1") (pin "1") (pinfunction "1_1") (pintype "passive"))
      (node (ref "LCD1") (pin "38") (pinfunction "CSB_38") (pintype "bidirectional"))
      (node (ref "R13") (pin "2") (pinfunction "2_2") (pintype "passive"))
    )
    (net (code "7") (name "DIR_1_MO_1") (class "Default")
      (node (ref "IC2") (pin "2") (pinfunction "1A_2") (pintype "input"))
      (node (ref "JP57") (pin "3") (pinfunction "3_3") (pintype "passive"))
    )
    (net (code "8") (name "DIR_1_MO_2") (class "Default")
      (node (ref "IC2") (pin "15") (pinfunction "4A_15") (pintype "input"))
      (node (ref "JP58") (pin "3") (pinfunction "3_3") (pintype "passive"))
    )
    (net (code "9") (name "DIR_2_MO_1") (class "Default")
      (node (ref "IC2") (pin "7") (pinfunction "2A_7") (pintype "input"))
      (node (ref "JP57") (pin "2") (pinfunction "2_2") (pintype "passive"))
    )
    (net (code "10") (name "DIR_2_MO_2") (class "Default")
      (node (ref "IC2") (pin "10") (pinfunction "3A_10") (pintype "input"))
      (node (ref "JP58") (pin "1") (pinfunction "1_1") (pintype "passive"))
    )
    (net (code "11") (name "GND") (class "Default")
      (node (ref "3V3") (pin "GND") (pinfunction "GND_GND") (pintype "bidirectional"))
      (node (ref "5V") (pin "GND") (pinfunction "GND_GND") (pintype "bidirectional"))
      (node (ref "C4") (pin "2") (pinfunction "2_2") (pintype "passive"))
      (node (ref "C5") (pin "2") (pinfunction "2_2") (pintype "passive"))
      (node (ref "C6") (pin "2") (pinfunction "2_2") (pintype "passive"))
      (node (ref "C7") (pin "-") (pinfunction "-_-") (pintype "passive"))
      (node (ref "D3") (pin "A") (pinfunction "A_A") (pintype "passive"))
      (node (ref "D4") (pin "A") (pinfunction "A_A") (pintype "passive"))
      (node (ref "D7") (pin "A") (pinfunction "A_A") (pintype "passive"))
      (node (ref "D8") (pin "A") (pinfunction "A_A") (pintype "passive"))
      (node (ref "IC1") (pin "8") (pinfunction "GND_8") (pintype "power_in"))
      (node (ref "IC2") (pin "12") (pinfunction "GND4_12") (pintype "power_in"))
      (node (ref "IC2") (pin "13") (pinfunction "GND3_13") (pintype "power_in"))
      (node (ref "IC2") (pin "4") (pinfunction "GND1_4") (pintype "power_in"))
      (node (ref "IC2") (pin "5") (pinfunction "GND2_5") (pintype "power_in"))
      (node (ref "JP42") (pin "1") (pinfunction "1_1") (pintype "passive"))
      (node (ref "JP42") (pin "2") (pinfunction "2_2") (pintype "passive"))
      (node (ref "JP42") (pin "3") (pinfunction "3_3") (pintype "passive"))
      (node (ref "JP42") (pin "4") (pinfunction "4_4") (pintype "passive"))
      (node (ref "JP44") (pin "2") (pinfunction "2_2") (pintype "passive"))
      (node (ref "JP56") (pin "17") (pinfunction "17_17") (pintype "passive"))
      (node (ref "JP56") (pin "18") (pinfunction "18_18") (pintype "passive"))
      (node (ref "JP67") (pin "1") (pinfunction "1_1") (pintype "passive"))
      (node (ref "JP67") (pin "2") (pinfunction "2_2") (pintype "passive"))
      (node (ref "JP67") (pin "3") (pinfunction "3_3") (pintype "passive"))
      (node (ref "JP67") (pin "4") (pinfunction "4_4") (pintype "passive"))
      (node (ref "JP67") (pin "5") (pinfunction "5_5") (pintype "passive"))
      (node (ref "JP67") (pin "6") (pinfunction "6_6") (pintype "passive"))
      (node (ref "JP67") (pin "7") (pinfunction "7_7") (pintype "passive"))
      (node (ref "JP67") (pin "8") (pinfunction "8_8") (pintype "passive"))
      (node (ref "LCD1") (pin "19") (pinfunction "C2-_19") (pintype "bidirectional"))
      (node (ref "LCD1") (pin "2") (pinfunction "C1-_2") (pintype "bidirectional"))
      (node (ref "LCD1") (pin "23") (pinfunction "PSB_23") (pintype "bidirectional"))
      (node (ref "LCD1") (pin "27") (pinfunction "VSS_27") (pintype "bidirectional"))
      (node (ref "R1") (pin "1") (pinfunction "1_1") (pintype "passive"))
      (node (ref "R11") (pin "1") (pinfunction "1_1") (pintype "passive"))
      (node (ref "R12") (pin "2") (pinfunction "2_2") (pintype "passive"))
      (node (ref "R13") (pin "1") (pinfunction "1_1") (pintype "passive"))
      (node (ref "R2") (pin "1") (pinfunction "1_1") (pintype "passive"))
      (node (ref "R3") (pin "1") (pinfunction "1_1") (pintype "passive"))
      (node (ref "R4") (pin "1") (pinfunction "1_1") (pintype "passive"))
      (node (ref "R6") (pin "2") (pinfunction "2_2") (pintype "passive"))
      (node (ref "R9") (pin "2") (pinfunction "2_2") (pintype "passive"))
      (node (ref "S1") (pin "1") (pinfunction "S_1") (pintype "passive"))
      (node (ref "S1") (pin "2") (pinfunction "S1_2") (pintype "passive"))
      (node (ref "S2") (pin "1") (pinfunction "S_1") (pintype "passive"))
      (node (ref "S2") (pin "2") (pinfunction "S1_2") (pintype "passive"))
      (node (ref "S3") (pin "1") (pinfunction "S_1") (pintype "passive"))
      (node (ref "S3") (pin "2") (pinfunction "S1_2") (pintype "passive"))
      (node (ref "S4") (pin "1") (pinfunction "S_1") (pintype "passive"))
      (node (ref "S4") (pin "2") (pinfunction "S1_2") (pintype "passive"))
      (node (ref "SW1") (pin "C") (pinfunction "C_C") (pintype "passive"))
      (node (ref "SW1") (pin "D") (pinfunction "1_D") (pintype "passive"))
      (node (ref "T1") (pin "1") (pinfunction "E_1") (pintype "passive"))
      (node (ref "U$7") (pin "2") (pinfunction "1_2") (pintype "bidirectional"))
      (node (ref "X1") (pin "2") (pinfunction "2_2") (pintype "passive"))
    )
    (net (code "12") (name "GND_BOARD_VL") (class "Default")
      (node (ref "JP14") (pin "1") (pinfunction "1_1") (pintype "passive"))
      (node (ref "JP15") (pin "3") (pinfunction "3_3") (pintype "passive"))
      (node (ref "JP16") (pin "25") (pinfunction "25_25") (pintype "passive"))
      (node (ref "JP19") (pin "1") (pinfunction "1_1") (pintype "passive"))
      (node (ref "JP44") (pin "1") (pinfunction "1_1") (pintype "passive"))
      (node (ref "U$1") (pin "GND_0_L_VL") (pinfunction "GND_0_L_VL_GND_0_L_VL") (pintype "bidirectional"))
      (node (ref "U$1") (pin "GND_1_L_VL") (pinfunction "GND_1_L_VL_GND_1_L_VL") (pintype "power_in"))
      (node (ref "U$1") (pin "GND_2_R_VL") (pinfunction "GND_2_R_VL_GND_2_R_VL") (pintype "bidirectional"))
      (node (ref "U$1") (pin "GND_3_R_VL") (pinfunction "GND_3_R_VL_GND_3_R_VL") (pintype "bidirectional"))
    )
    (net (code "13") (name "GNUB_3V3") (class "Default")
      (node (ref "JP64") (pin "13") (pinfunction "13_13") (pintype "passive"))
      (node (ref "SV3") (pin "13") (pinfunction "13_13") (pintype "passive"))
    )
    (net (code "14") (name "GNUB_GND") (class "Default")
      (node (ref "JP64") (pin "14") (pinfunction "14_14") (pintype "passive"))
      (node (ref "SV3") (pin "14") (pinfunction "14_14") (pintype "passive"))
    )
    (net (code "15") (name "GNUB_GPA0") (class "Default")
      (node (ref "JP64") (pin "1") (pinfunction "1_1") (pintype "passive"))
      (node (ref "SV3") (pin "1") (pinfunction "1_1") (pintype "passive"))
    )
    (net (code "16") (name "GNUB_GPA1") (class "Default")
      (node (ref "JP64") (pin "2") (pinfunction "2_2") (pintype "passive"))
      (node (ref "SV3") (pin "2") (pinfunction "2_2") (pintype "passive"))
    )
    (net (code "17") (name "GNUB_GPA3") (class "Default")
      (node (ref "JP64") (pin "3") (pinfunction "3_3") (pintype "passive"))
      (node (ref "SV3") (pin "3") (pinfunction "3_3") (pintype "passive"))
    )
    (net (code "18") (name "GNUB_GPIO11") (class "Default")
      (node (ref "JP64") (pin "12") (pinfunction "12_12") (pintype "passive"))
      (node (ref "SV3") (pin "12") (pinfunction "12_12") (pintype "passive"))
    )
    (net (code "19") (name "GNUB_GPIO14") (class "Default")
      (node (ref "JP64") (pin "11") (pinfunction "11_11") (pintype "passive"))
      (node (ref "SV3") (pin "11") (pinfunction "11_11") (pintype "passive"))
    )
    (net (code "20") (name "GNUB_MISO") (class "Default")
      (node (ref "JP64") (pin "8") (pinfunction "8_8") (pintype "passive"))
      (node (ref "SV3") (pin "8") (pinfunction "8_8") (pintype "passive"))
    )
    (net (code "21") (name "GNUB_MOSI") (class "Default")
      (node (ref "JP64") (pin "7") (pinfunction "7_7") (pintype "passive"))
      (node (ref "SV3") (pin "7") (pinfunction "7_7") (pintype "passive"))
    )
    (net (code "22") (name "GNUB_PWM_DATA") (class "Default")
      (node (ref "JP64") (pin "4") (pinfunction "4_4") (pintype "passive"))
      (node (ref "SV3") (pin "4") (pinfunction "4_4") (pintype "passive"))
    )
    (net (code "23") (name "GNUB_SCK") (class "Default")
      (node (ref "JP64") (pin "10") (pinfunction "10_10") (pintype "passive"))
      (node (ref "SV3") (pin "10") (pinfunction "10_10") (pintype "passive"))
    )
    (net (code "24") (name "GNUB_SCL") (class "Default")
      (node (ref "JP64") (pin "5") (pinfunction "5_5") (pintype "passive"))
      (node (ref "SV3") (pin "5") (pinfunction "5_5") (pintype "passive"))
    )
    (net (code "25") (name "GNUB_SDA") (class "Default")
      (node (ref "JP64") (pin "6") (pinfunction "6_6") (pintype "passive"))
      (node (ref "SV3") (pin "6") (pinfunction "6_6") (pintype "passive"))
    )
    (net (code "26") (name "GNUB_SYSCLOCK_0") (class "Default")
      (node (ref "JP64") (pin "9") (pinfunction "9_9") (pintype "passive"))
      (node (ref "SV3") (pin "9") (pinfunction "9_9") (pintype "passive"))
    )
    (net (code "27") (name "MCO_VL") (class "Default")
      (node (ref "JP14") (pin "23") (pinfunction "23_23") (pintype "passive"))
      (node (ref "MCO") (pin "1") (pinfunction "1_1") (pintype "passive"))
      (node (ref "U$1") (pin "PA8_VL") (pinfunction "PA8_VL_PA8_VL") (pintype "bidirectional"))
    )
    (net (code "28") (name "MOTOR_VCC") (class "Default")
      (node (ref "C5") (pin "1") (pinfunction "1_1") (pintype "passive"))
      (node (ref "C7") (pin "+") (pinfunction "+_+") (pintype "passive"))
      (node (ref "D1") (pin "C") (pinfunction "C_C") (pintype "passive"))
      (node (ref "D2") (pin "C") (pinfunction "C_C") (pintype "passive"))
      (node (ref "D5") (pin "C") (pinfunction "C_C") (pintype "passive"))
      (node (ref "D6") (pin "C") (pinfunction "C_C") (pintype "passive"))
      (node (ref "IC2") (pin "8") (pinfunction "VCC2_8") (pintype "power_in"))
      (node (ref "U$4") (pin "1") (pinfunction "1_1") (pintype "bidirectional"))
      (node (ref "X1") (pin "1") (pinfunction "1_1") (pintype "passive"))
    )
    (net (code "29") (name "Net-(IC1-I1)") (class "Default")
      (node (ref "IC1") (pin "1") (pinfunction "I1_1") (pintype "input"))
      (node (ref "JP26") (pin "1") (pinfunction "1_1") (pintype "passive"))
    )
    (net (code "30") (name "Net-(IC1-I2)") (class "Default")
      (node (ref "IC1") (pin "2") (pinfunction "I2_2") (pintype "input"))
      (node (ref "JP26") (pin "2") (pinfunction "2_2") (pintype "passive"))
    )
    (net (code "31") (name "Net-(IC1-I3)") (class "Default")
      (node (ref "IC1") (pin "3") (pinfunction "I3_3") (pintype "input"))
      (node (ref "JP26") (pin "3") (pinfunction "3_3") (pintype "passive"))
    )
    (net (code "32") (name "Net-(IC1-I4)") (class "Default")
      (node (ref "IC1") (pin "4") (pinfunction "I4_4") (pintype "input"))
      (node (ref "JP26") (pin "4") (pinfunction "4_4") (pintype "passive"))
    )
    (net (code "33") (name "Net-(IC1-I5)") (class "Default")
      (node (ref "IC1") (pin "5") (pinfunction "I5_5") (pintype "input"))
      (node (ref "JP26") (pin "5") (pinfunction "5_5") (pintype "passive"))
    )
    (net (code "34") (name "Net-(IC1-I6)") (class "Default")
      (node (ref "IC1") (pin "6") (pinfunction "I6_6") (pintype "input"))
      (node (ref "JP26") (pin "6") (pinfunction "6_6") (pintype "passive"))
    )
    (net (code "35") (name "Net-(IC1-I7)") (class "Default")
      (node (ref "IC1") (pin "7") (pinfunction "I7_7") (pintype "input"))
      (node (ref "JP26") (pin "7") (pinfunction "7_7") (pintype "passive"))
    )
    (net (code "36") (name "Net-(IC1-O1)") (class "Default")
      (node (ref "IC1") (pin "16") (pinfunction "O1_16") (pintype "open_collector"))
      (node (ref "JP21") (pin "1") (pinfunction "1_1") (pintype "passive"))
      (node (ref "JP25") (pin "2") (pinfunction "2_2") (pintype "passive"))
      (node (ref "R32") (pin "1") (pinfunction "1_1") (pintype "passive"))
    )
    (net (code "37") (name "Net-(IC1-O2)") (class "Default")
      (node (ref "IC1") (pin "15") (pinfunction "O2_15") (pintype "open_collector"))
      (node (ref "JP21") (pin "2") (pinfunction "2_2") (pintype "passive"))
      (node (ref "JP25") (pin "3") (pinfunction "3_3") (pintype "passive"))
      (node (ref "R34") (pin "1") (pinfunction "1_1") (pintype "passive"))
    )
    (net (code "38") (name "Net-(IC1-O3)") (class "Default")
      (node (ref "IC1") (pin "14") (pinfunction "O3_14") (pintype "open_collector"))
      (node (ref "JP21") (pin "3") (pinfunction "3_3") (pintype "passive"))
      (node (ref "JP25") (pin "4") (pinfunction "4_4") (pintype "passive"))
      (node (ref "R33") (pin "1") (pinfunction "1_1") (pintype "passive"))
    )
    (net (code "39") (name "Net-(IC1-O4)") (class "Default")
      (node (ref "IC1") (pin "13") (pinfunction "O4_13") (pintype "open_collector"))
      (node (ref "JP21") (pin "4") (pinfunction "4_4") (pintype "passive"))
      (node (ref "JP25") (pin "5") (pinfunction "5_5") (pintype "passive"))
      (node (ref "R35") (pin "1") (pinfunction "1_1") (pintype "passive"))
    )
    (net (code "40") (name "Net-(IC1-O5)") (class "Default")
      (node (ref "IC1") (pin "12") (pinfunction "O5_12") (pintype "open_collector"))
      (node (ref "JP21") (pin "5") (pinfunction "5_5") (pintype "passive"))
    )
    (net (code "41") (name "Net-(IC1-O6)") (class "Default")
      (node (ref "IC1") (pin "11") (pinfunction "O6_11") (pintype "open_collector"))
      (node (ref "JP21") (pin "6") (pinfunction "6_6") (pintype "passive"))
    )
    (net (code "42") (name "Net-(IC1-O7)") (class "Default")
      (node (ref "IC1") (pin "10") (pinfunction "O7_10") (pintype "open_collector"))
      (node (ref "JP21") (pin "7") (pinfunction "7_7") (pintype "passive"))
    )
    (net (code "43") (name "Net-(IC2-1Y)") (class "Default")
      (node (ref "D6") (pin "A") (pinfunction "A_A") (pintype "passive"))
      (node (ref "D8") (pin "C") (pinfunction "C_C") (pintype "passive"))
      (node (ref "IC2") (pin "3") (pinfunction "1Y_3") (pintype "output"))
      (node (ref "K2") (pin "1") (pinfunction "1_1") (pintype "passive"))
    )
    (net (code "44") (name "Net-(IC2-2Y)") (class "Default")
      (node (ref "D5") (pin "A") (pinfunction "A_A") (pintype "passive"))
      (node (ref "D7") (pin "C") (pinfunction "C_C") (pintype "passive"))
      (node (ref "IC2") (pin "6") (pinfunction "2Y_6") (pintype "output"))
      (node (ref "K2") (pin "2") (pinfunction "2_2") (pintype "passive"))
    )
    (net (code "45") (name "Net-(IC2-3Y)") (class "Default")
      (node (ref "D1") (pin "A") (pinfunction "A_A") (pintype "passive"))
      (node (ref "D3") (pin "C") (pinfunction "C_C") (pintype "passive"))
      (node (ref "IC2") (pin "11") (pinfunction "3Y_11") (pintype "output"))
      (node (ref "K1") (pin "1") (pinfunction "1_1") (pintype "passive"))
    )
    (net (code "46") (name "Net-(IC2-4Y)") (class "Default")
      (node (ref "D2") (pin "A") (pinfunction "A_A") (pintype "passive"))
      (node (ref "D4") (pin "C") (pinfunction "C_C") (pintype "passive"))
      (node (ref "IC2") (pin "14") (pinfunction "4Y_14") (pintype "output"))
      (node (ref "K1") (pin "2") (pinfunction "2_2") (pintype "passive"))
    )
    (net (code "47") (name "Net-(JP2-Pad1)") (class "Default")
      (node (ref "JP2") (pin "1") (pinfunction "1_1") (pintype "passive"))
      (node (ref "R19") (pin "1") (pinfunction "1_1") (pintype "passive"))
      (node (ref "SW1") (pin "A") (pinfunction "A_A") (pintype "passive"))
    )
    (net (code "48") (name "Net-(JP3-Pad1)") (class "Default")
      (node (ref "JP3") (pin "1") (pinfunction "1_1") (pintype "passive"))
      (node (ref "R18") (pin "2") (pinfunction "2_2") (pintype "passive"))
      (node (ref "SW1") (pin "B") (pinfunction "B_B") (pintype "passive"))
    )
    (net (code "49") (name "Net-(JP4-Pad2)") (class "Default")
      (node (ref "JP4") (pin "2") (pinfunction "2_2") (pintype "passive"))
      (node (ref "LED5") (pin "A") (pinfunction "A_A") (pintype "passive"))
    )
    (net (code "50") (name "Net-(JP5-Pad1)") (class "Default")
      (node (ref "JP5") (pin "1") (pinfunction "1_1") (pintype "passive"))
      (node (ref "LED1") (pin "A") (pinfunction "A_A") (pintype "passive"))
    )
    (net (code "51") (name "Net-(JP6-Pad1)") (class "Default")
      (node (ref "JP6") (pin "1") (pinfunction "1_1") (pintype "passive"))
      (node (ref "LED2") (pin "A") (pinfunction "A_A") (pintype "passive"))
    )
    (net (code "52") (name "Net-(JP7-Pad1)") (class "Default")
      (node (ref "JP7") (pin "1") (pinfunction "1_1") (pintype "passive"))
      (node (ref "LED3") (pin "A") (pinfunction "A_A") (pintype "passive"))
    )
    (net (code "53") (name "Net-(JP8-Pad1)") (class "Default")
      (node (ref "JP8") (pin "1") (pinfunction "1_1") (pintype "passive"))
      (node (ref "LED4") (pin "A") (pinfunction "A_A") (pintype "passive"))
    )
    (net (code "54") (name "Net-(JP14-Pad2)") (class "Default")
      (node (ref "JP14") (pin "2") (pinfunction "2_2") (pintype "passive"))
      (node (ref "U$1") (pin "NC_R_VL") (pinfunction "NC_R_VL_NC_R_VL") (pintype "bidirectional"))
    )
    (net (code "55") (name "Net-(JP14-Pad4)") (class "Default")
      (node (ref "JP14") (pin "4") (pinfunction "4_4") (pintype "passive"))
      (node (ref "U$1") (pin "PB9_VL") (pinfunction "PB9_VL_PB9_VL") (pintype "bidirectional"))
    )
    (net (code "56") (name "Net-(JP14-Pad5)") (class "Default")
      (node (ref "JP14") (pin "5") (pinfunction "5_5") (pintype "passive"))
      (node (ref "U$1") (pin "PB8_VL") (pinfunction "PB8_VL_PB8_VL") (pintype "bidirectional"))
    )
    (net (code "57") (name "Net-(JP14-Pad6)") (class "Default")
      (node (ref "JP14") (pin "6") (pinfunction "6_6") (pintype "passive"))
      (node (ref "U$1") (pin "BOOT0_VL") (pinfunction "BOOT0_VL_BOOT0_VL") (pintype "bidirectional"))
    )
    (net (code "58") (name "Net-(JP14-Pad7)") (class "Default")
      (node (ref "JP14") (pin "7") (pinfunction "7_7") (pintype "passive"))
      (node (ref "U$1") (pin "PB7_VL") (pinfunction "PB7_VL_PB7_VL") (pintype "bidirectional"))
    )
    (net (code "59") (name "Net-(JP14-Pad8)") (class "Default")
      (node (ref "JP14") (pin "8") (pinfunction "8_8") (pintype "passive"))
      (node (ref "U$1") (pin "PB6_VL") (pinfunction "PB6_VL_PB6_VL") (pintype "bidirectional"))
    )
    (net (code "60") (name "Net-(JP14-Pad9)") (class "Default")
      (node (ref "JP14") (pin "9") (pinfunction "9_9") (pintype "passive"))
      (node (ref "U$1") (pin "PB5_VL") (pinfunction "PB5_VL_PB5_VL") (pintype "bidirectional"))
    )
    (net (code "61") (name "Net-(JP14-Pad10)") (class "Default")
      (node (ref "JP14") (pin "10") (pinfunction "10_10") (pintype "passive"))
      (node (ref "U$1") (pin "PB4_VL") (pinfunction "PB4_VL_PB4_VL") (pintype "bidirectional"))
    )
    (net (code "62") (name "Net-(JP14-Pad11)") (class "Default")
      (node (ref "JP14") (pin "11") (pinfunction "11_11") (pintype "passive"))
      (node (ref "U$1") (pin "PB3_VL") (pinfunction "PB3_VL_PB3_VL") (pintype "bidirectional"))
    )
    (net (code "63") (name "Net-(JP14-Pad12)") (class "Default")
      (node (ref "JP14") (pin "12") (pinfunction "12_12") (pintype "passive"))
      (node (ref "U$1") (pin "PD2_VL") (pinfunction "PD2_VL_PD2_VL") (pintype "bidirectional"))
    )
    (net (code "64") (name "Net-(JP14-Pad13)") (class "Default")
      (node (ref "JP14") (pin "13") (pinfunction "13_13") (pintype "passive"))
      (node (ref "U$1") (pin "PC12_VL") (pinfunction "PC12_VL_PC12_VL") (pintype "bidirectional"))
    )
    (net (code "65") (name "Net-(JP14-Pad14)") (class "Default")
      (node (ref "JP14") (pin "14") (pinfunction "14_14") (pintype "passive"))
      (node (ref "U$1") (pin "PC11_VL") (pinfunction "PC11_VL_PC11_VL") (pintype "bidirectional"))
    )
    (net (code "66") (name "Net-(JP14-Pad15)") (class "Default")
      (node (ref "JP14") (pin "15") (pinfunction "15_15") (pintype "passive"))
      (node (ref "U$1") (pin "PC10_VL") (pinfunction "PC10_VL_PC10_VL") (pintype "bidirectional"))
    )
    (net (code "67") (name "Net-(JP14-Pad16)") (class "Default")
      (node (ref "JP14") (pin "16") (pinfunction "16_16") (pintype "passive"))
      (node (ref "U$1") (pin "PA15_VL") (pinfunction "PA15_VL_PA15_VL") (pintype "bidirectional"))
    )
    (net (code "68") (name "Net-(JP14-Pad17)") (class "Default")
      (node (ref "JP14") (pin "17") (pinfunction "17_17") (pintype "passive"))
      (node (ref "U$1") (pin "PA14_VL") (pinfunction "PA14_VL_PA14_VL") (pintype "bidirectional"))
    )
    (net (code "69") (name "Net-(JP14-Pad18)") (class "Default")
      (node (ref "JP14") (pin "18") (pinfunction "18_18") (pintype "passive"))
      (node (ref "U$1") (pin "PA13_VL") (pinfunction "PA13_VL_PA13_VL") (pintype "bidirectional"))
    )
    (net (code "70") (name "Net-(JP14-Pad19)") (class "Default")
      (node (ref "JP14") (pin "19") (pinfunction "19_19") (pintype "passive"))
      (node (ref "U$1") (pin "PA12_VL") (pinfunction "PA12_VL_PA12_VL") (pintype "bidirectional"))
    )
    (net (code "71") (name "Net-(JP14-Pad20)") (class "Default")
      (node (ref "JP14") (pin "20") (pinfunction "20_20") (pintype "passive"))
      (node (ref "U$1") (pin "PA11_VL") (pinfunction "PA11_VL_PA11_VL") (pintype "bidirectional"))
    )
    (net (code "72") (name "Net-(JP14-Pad21)") (class "Default")
      (node (ref "JP14") (pin "21") (pinfunction "21_21") (pintype "passive"))
      (node (ref "U$1") (pin "PA10_VL") (pinfunction "PA10_VL_PA10_VL") (pintype "bidirectional"))
    )
    (net (code "73") (name "Net-(JP14-Pad22)") (class "Default")
      (node (ref "JP14") (pin "22") (pinfunction "22_22") (pintype "passive"))
      (node (ref "U$1") (pin "PA9_VL") (pinfunction "PA9_VL_PA9_VL") (pintype "bidirectional"))
    )
    (net (code "74") (name "Net-(JP14-Pad24)") (class "Default")
      (node (ref "JP14") (pin "24") (pinfunction "24_24") (pintype "passive"))
      (node (ref "U$1") (pin "PC9_VL") (pinfunction "PC9_VL_PC9_VL") (pintype "bidirectional"))
    )
    (net (code "75") (name "Net-(JP14-Pad25)") (class "Default")
      (node (ref "JP14") (pin "25") (pinfunction "25_25") (pintype "passive"))
      (node (ref "U$1") (pin "PC8_VL") (pinfunction "PC8_VL_PC8_VL") (pintype "bidirectional"))
    )
    (net (code "76") (name "Net-(JP15-Pad1)") (class "Default")
      (node (ref "JP15") (pin "1") (pinfunction "1_1") (pintype "passive"))
      (node (ref "U$1") (pin "PC7_VL") (pinfunction "PC7_VL_PC7_VL") (pintype "bidirectional"))
    )
    (net (code "77") (name "Net-(JP15-Pad2)") (class "Default")
      (node (ref "JP15") (pin "2") (pinfunction "2_2") (pintype "passive"))
      (node (ref "U$1") (pin "PC6_VL") (pinfunction "PC6_VL_PC6_VL") (pintype "bidirectional"))
    )
    (net (code "78") (name "Net-(JP16-Pad1)") (class "Default")
      (node (ref "JP16") (pin "1") (pinfunction "1_1") (pintype "passive"))
      (node (ref "U$1") (pin "PB0_VL") (pinfunction "PB0_VL_PB0_VL") (pintype "bidirectional"))
    )
    (net (code "79") (name "Net-(JP16-Pad2)") (class "Default")
      (node (ref "JP16") (pin "2") (pinfunction "2_2") (pintype "passive"))
      (node (ref "U$1") (pin "PC5_VL") (pinfunction "PC5_VL_PC5_VL") (pintype "bidirectional"))
    )
    (net (code "80") (name "Net-(JP16-Pad3)") (class "Default")
      (node (ref "JP16") (pin "3") (pinfunction "3_3") (pintype "passive"))
      (node (ref "U$1") (pin "PC4_VL") (pinfunction "PC4_VL_PC4_VL") (pintype "bidirectional"))
    )
    (net (code "81") (name "Net-(JP16-Pad4)") (class "Default")
      (node (ref "JP16") (pin "4") (pinfunction "4_4") (pintype "passive"))
      (node (ref "U$1") (pin "PA7_VL") (pinfunction "PA7_VL_PA7_VL") (pintype "bidirectional"))
    )
    (net (code "82") (name "Net-(JP16-Pad5)") (class "Default")
      (node (ref "JP16") (pin "5") (pinfunction "5_5") (pintype "passive"))
      (node (ref "U$1") (pin "PA6_VL") (pinfunction "PA6_VL_PA6_VL") (pintype "bidirectional"))
    )
    (net (code "83") (name "Net-(JP16-Pad6)") (class "Default")
      (node (ref "JP16") (pin "6") (pinfunction "6_6") (pintype "passive"))
      (node (ref "U$1") (pin "PA5_VL") (pinfunction "PA5_VL_PA5_VL") (pintype "bidirectional"))
    )
    (net (code "84") (name "Net-(JP16-Pad7)") (class "Default")
      (node (ref "JP16") (pin "7") (pinfunction "7_7") (pintype "passive"))
      (node (ref "U$1") (pin "PA4_VL") (pinfunction "PA4_VL_PA4_VL") (pintype "bidirectional"))
    )
    (net (code "85") (name "Net-(JP16-Pad8)") (class "Default")
      (node (ref "JP16") (pin "8") (pinfunction "8_8") (pintype "passive"))
      (node (ref "U$1") (pin "PA3_VL") (pinfunction "PA3_VL_PA3_VL") (pintype "bidirectional"))
    )
    (net (code "86") (name "Net-(JP16-Pad9)") (class "Default")
      (node (ref "JP16") (pin "9") (pinfunction "9_9") (pintype "passive"))
      (node (ref "U$1") (pin "PA2_VL") (pinfunction "PA2_VL_PA2_VL") (pintype "bidirectional"))
    )
    (net (code "87") (name "Net-(JP16-Pad10)") (class "Default")
      (node (ref "JP16") (pin "10") (pinfunction "10_10") (pintype "passive"))
      (node (ref "U$1") (pin "PA1_VL") (pinfunction "PA1_VL_PA1_VL") (pintype "bidirectional"))
    )
    (net (code "88") (name "Net-(JP16-Pad11)") (class "Default")
      (node (ref "JP16") (pin "11") (pinfunction "11_11") (pintype "passive"))
      (node (ref "U$1") (pin "PA0_VL") (pinfunction "PA0_VL_PA0_VL") (pintype "bidirectional"))
    )
    (net (code "89") (name "Net-(JP16-Pad12)") (class "Default")
      (node (ref "JP16") (pin "12") (pinfunction "12_12") (pintype "passive"))
      (node (ref "U$1") (pin "PC3_VL") (pinfunction "PC3_VL_PC3_VL") (pintype "bidirectional"))
    )
    (net (code "90") (name "Net-(JP16-Pad13)") (class "Default")
      (node (ref "JP16") (pin "13") (pinfunction "13_13") (pintype "passive"))
      (node (ref "U$1") (pin "PC2_VL") (pinfunction "PC2_VL_PC2_VL") (pintype "bidirectional"))
    )
    (net (code "91") (name "Net-(JP16-Pad14)") (class "Default")
      (node (ref "JP16") (pin "14") (pinfunction "14_14") (pintype "passive"))
      (node (ref "U$1") (pin "PC1_VL") (pinfunction "PC1_VL_PC1_VL") (pintype "bidirectional"))
    )
    (net (code "92") (name "Net-(JP16-Pad15)") (class "Default")
      (node (ref "JP16") (pin "15") (pinfunction "15_15") (pintype "passive"))
      (node (ref "U$1") (pin "PC0_VL") (pinfunction "PC0_VL_PC0_VL") (pintype "bidirectional"))
    )
    (net (code "93") (name "Net-(JP16-Pad17)") (class "Default")
      (node (ref "JP16") (pin "17") (pinfunction "17_17") (pintype "passive"))
      (node (ref "U$1") (pin "PD1_VL") (pinfunction "PD1_VL_PD1_VL") (pintype "bidirectional"))
    )
    (net (code "94") (name "Net-(JP16-Pad18)") (class "Default")
      (node (ref "JP16") (pin "18") (pinfunction "18_18") (pintype "passive"))
      (node (ref "U$1") (pin "PD0_VL") (pinfunction "PD0_VL_PD0_VL") (pintype "bidirectional"))
    )
    (net (code "95") (name "Net-(JP16-Pad19)") (class "Default")
      (node (ref "JP16") (pin "19") (pinfunction "19_19") (pintype "passive"))
      (node (ref "U$1") (pin "PC15_VL") (pinfunction "PC15_VL_PC15_VL") (pintype "bidirectional"))
    )
    (net (code "96") (name "Net-(JP16-Pad20)") (class "Default")
      (node (ref "JP16") (pin "20") (pinfunction "20_20") (pintype "passive"))
      (node (ref "U$1") (pin "PC14_VL") (pinfunction "PC14_VL_PC14_VL") (pintype "bidirectional"))
    )
    (net (code "97") (name "Net-(JP16-Pad21)") (class "Default")
      (node (ref "JP16") (pin "21") (pinfunction "21_21") (pintype "passive"))
      (node (ref "U$1") (pin "PC13_VL") (pinfunction "PC13_VL_PC13_VL") (pintype "bidirectional"))
    )
    (net (code "98") (name "Net-(JP16-Pad24)") (class "Default")
      (node (ref "JP16") (pin "24") (pinfunction "24_24") (pintype "passive"))
      (node (ref "U$1") (pin "NC_L_VL") (pinfunction "NC_L_VL_NC_L_VL") (pintype "bidirectional"))
    )
    (net (code "99") (name "Net-(JP17-Pad1)") (class "Default")
      (node (ref "JP17") (pin "1") (pinfunction "1_1") (pintype "passive"))
      (node (ref "R21") (pin "2") (pinfunction "2_2") (pintype "passive"))
    )
    (net (code "100") (name "Net-(JP18-Pad1)") (class "Default")
      (node (ref "JP18") (pin "1") (pinfunction "1_1") (pintype "passive"))
      (node (ref "JP75") (pin "1") (pinfunction "1_1") (pintype "passive"))
      (node (ref "R5") (pin "1") (pinfunction "1_1") (pintype "passive"))
    )
    (net (code "101") (name "Net-(JP19-Pad2)") (class "Default")
      (node (ref "JP19") (pin "2") (pinfunction "2_2") (pintype "passive"))
      (node (ref "U$1") (pin "PB2_VL") (pinfunction "PB2_VL_PB2_VL") (pintype "bidirectional"))
    )
    (net (code "102") (name "Net-(JP19-Pad3)") (class "Default")
      (node (ref "JP19") (pin "3") (pinfunction "3_3") (pintype "passive"))
      (node (ref "U$1") (pin "PB1_VL") (pinfunction "PB1_VL_PB1_VL") (pintype "bidirectional"))
    )
    (net (code "103") (name "Net-(JP22-Pad1)") (class "Default")
      (node (ref "JP22") (pin "1") (pinfunction "1_1") (pintype "passive"))
      (node (ref "R31") (pin "1") (pinfunction "1_1") (pintype "passive"))
    )
    (net (code "104") (name "Net-(JP22-Pad2)") (class "Default")
      (node (ref "JP22") (pin "2") (pinfunction "2_2") (pintype "passive"))
      (node (ref "R30") (pin "1") (pinfunction "1_1") (pintype "passive"))
    )
    (net (code "105") (name "Net-(JP22-Pad3)") (class "Default")
      (node (ref "JP22") (pin "3") (pinfunction "3_3") (pintype "passive"))
      (node (ref "R29") (pin "1") (pinfunction "1_1") (pintype "passive"))
    )
    (net (code "106") (name "Net-(JP22-Pad4)") (class "Default")
      (node (ref "JP22") (pin "4") (pinfunction "4_4") (pintype "passive"))
      (node (ref "R28") (pin "1") (pinfunction "1_1") (pintype "passive"))
    )
    (net (code "107") (name "Net-(JP22-Pad5)") (class "Default")
      (node (ref "JP22") (pin "5") (pinfunction "5_5") (pintype "passive"))
      (node (ref "R27") (pin "1") (pinfunction "1_1") (pintype "passive"))
    )
    (net (code "108") (name "Net-(JP22-Pad6)") (class "Default")
      (node (ref "JP22") (pin "6") (pinfunction "6_6") (pintype "passive"))
      (node (ref "R26") (pin "1") (pinfunction "1_1") (pintype "passive"))
    )
    (net (code "109") (name "Net-(JP22-Pad7)") (class "Default")
      (node (ref "JP22") (pin "7") (pinfunction "7_7") (pintype "passive"))
      (node (ref "R25") (pin "1") (pinfunction "1_1") (pintype "passive"))
    )
    (net (code "110") (name "Net-(JP22-Pad8)") (class "Default")
      (node (ref "JP22") (pin "8") (pinfunction "8_8") (pintype "passive"))
      (node (ref "R24") (pin "1") (pinfunction "1_1") (pintype "passive"))
    )
    (net (code "111") (name "Net-(JP23-Pad1)") (class "Default")
      (node (ref "JP23") (pin "1") (pinfunction "1_1") (pintype "passive"))
      (node (ref "LED8") (pin "1") (pinfunction "A_1") (pintype "passive"))
      (node (ref "LED8") (pin "6") (pinfunction "A_6") (pintype "passive"))
    )
    (net (code "112") (name "Net-(JP24-Pad1)") (class "Default")
      (node (ref "JP24") (pin "1") (pinfunction "1_1") (pintype "passive"))
      (node (ref "JP27") (pin "4") (pinfunction "4_4") (pintype "passive"))
    )
    (net (code "113") (name "Net-(JP24-Pad2)") (class "Default")
      (node (ref "JP24") (pin "2") (pinfunction "2_2") (pintype "passive"))
      (node (ref "JP27") (pin "3") (pinfunction "3_3") (pintype "passive"))
    )
    (net (code "114") (name "Net-(JP24-Pad3)") (class "Default")
      (node (ref "JP24") (pin "3") (pinfunction "3_3") (pintype "passive"))
      (node (ref "JP27") (pin "2") (pinfunction "2_2") (pintype "passive"))
    )
    (net (code "115") (name "Net-(JP24-Pad4)") (class "Default")
      (node (ref "JP24") (pin "4") (pinfunction "4_4") (pintype "passive"))
      (node (ref "JP27") (pin "1") (pinfunction "1_1") (pintype "passive"))
    )
    (net (code "116") (name "Net-(JP45-Pad1)") (class "Default")
      (node (ref "JP45") (pin "1") (pinfunction "1_1") (pintype "passive"))
      (node (ref "JP45") (pin "2") (pinfunction "2_2") (pintype "passive"))
      (node (ref "JP45") (pin "3") (pinfunction "3_3") (pintype "passive"))
      (node (ref "JP45") (pin "4") (pinfunction "4_4") (pintype "passive"))
      (node (ref "JP45") (pin "5") (pinfunction "5_5") (pintype "passive"))
      (node (ref "JP45") (pin "6") (pinfunction "6_6") (pintype "passive"))
      (node (ref "JP45") (pin "7") (pinfunction "7_7") (pintype "passive"))
      (node (ref "JP45") (pin "8") (pinfunction "8_8") (pintype "passive"))
    )
    (net (code "117") (name "Net-(JP46-Pad1)") (class "Default")
      (node (ref "JP46") (pin "1") (pinfunction "1_1") (pintype "passive"))
      (node (ref "U$1") (pin "PB15_VL") (pinfunction "PB15_VL_PB15_VL") (pintype "bidirectional"))
    )
    (net (code "118") (name "Net-(JP46-Pad2)") (class "Default")
      (node (ref "JP46") (pin "2") (pinfunction "2_2") (pintype "passive"))
      (node (ref "U$1") (pin "PB14_VL") (pinfunction "PB14_VL_PB14_VL") (pintype "bidirectional"))
    )
    (net (code "119") (name "Net-(JP46-Pad3)") (class "Default")
      (node (ref "JP46") (pin "3") (pinfunction "3_3") (pintype "passive"))
      (node (ref "U$1") (pin "PB13_VL") (pinfunction "PB13_VL_PB13_VL") (pintype "bidirectional"))
    )
    (net (code "120") (name "Net-(JP49-Pad1)") (class "Default")
      (node (ref "JP49") (pin "1") (pinfunction "1_1") (pintype "passive"))
      (node (ref "JP50") (pin "3") (pinfunction "3_3") (pintype "passive"))
    )
    (net (code "121") (name "Net-(JP49-Pad2)") (class "Default")
      (node (ref "JP49") (pin "2") (pinfunction "2_2") (pintype "passive"))
      (node (ref "JP50") (pin "2") (pinfunction "2_2") (pintype "passive"))
    )
    (net (code "122") (name "Net-(JP49-Pad3)") (class "Default")
      (node (ref "JP49") (pin "3") (pinfunction "3_3") (pintype "passive"))
      (node (ref "JP50") (pin "1") (pinfunction "1_1") (pintype "passive"))
    )
    (net (code "123") (name "Net-(JP51-Pad1)") (class "Default")
      (node (ref "JP51") (pin "1") (pinfunction "1_1") (pintype "passive"))
      (node (ref "JP52") (pin "3") (pinfunction "3_3") (pintype "passive"))
    )
    (net (code "124") (name "Net-(JP51-Pad2)") (class "Default")
      (node (ref "JP51") (pin "2") (pinfunction "2_2") (pintype "passive"))
      (node (ref "JP52") (pin "2") (pinfunction "2_2") (pintype "passive"))
    )
    (net (code "125") (name "Net-(JP51-Pad3)") (class "Default")
      (node (ref "JP51") (pin "3") (pinfunction "3_3") (pintype "passive"))
      (node (ref "JP52") (pin "1") (pinfunction "1_1") (pintype "passive"))
    )
    (net (code "126") (name "Net-(JP56-Pad1)") (class "Default")
      (node (ref "JP56") (pin "1") (pinfunction "1_1") (pintype "passive"))
      (node (ref "JP56") (pin "2") (pinfunction "2_2") (pintype "passive"))
    )
    (net (code "127") (name "Net-(JP56-Pad3)") (class "Default")
      (node (ref "JP56") (pin "3") (pinfunction "3_3") (pintype "passive"))
      (node (ref "JP56") (pin "4") (pinfunction "4_4") (pintype "passive"))
    )
    (net (code "128") (name "Net-(JP56-Pad5)") (class "Default")
      (node (ref "JP56") (pin "5") (pinfunction "5_5") (pintype "passive"))
      (node (ref "JP56") (pin "6") (pinfunction "6_6") (pintype "passive"))
    )
    (net (code "129") (name "Net-(JP56-Pad7)") (class "Default")
      (node (ref "JP56") (pin "7") (pinfunction "7_7") (pintype "passive"))
      (node (ref "JP56") (pin "8") (pinfunction "8_8") (pintype "passive"))
    )
    (net (code "130") (name "Net-(JP56-Pad10)") (class "Default")
      (node (ref "JP56") (pin "10") (pinfunction "10_10") (pintype "passive"))
      (node (ref "JP56") (pin "9") (pinfunction "9_9") (pintype "passive"))
    )
    (net (code "131") (name "Net-(JP56-Pad11)") (class "Default")
      (node (ref "JP56") (pin "11") (pinfunction "11_11") (pintype "passive"))
      (node (ref "JP56") (pin "12") (pinfunction "12_12") (pintype "passive"))
    )
    (net (code "132") (name "Net-(JP56-Pad13)") (class "Default")
      (node (ref "JP56") (pin "13") (pinfunction "13_13") (pintype "passive"))
      (node (ref "JP56") (pin "14") (pinfunction "14_14") (pintype "passive"))
    )
    (net (code "133") (name "Net-(JP56-Pad15)") (class "Default")
      (node (ref "JP56") (pin "15") (pinfunction "15_15") (pintype "passive"))
      (node (ref "JP56") (pin "16") (pinfunction "16_16") (pintype "passive"))
    )
    (net (code "134") (name "Net-(JP59-Pad2)") (class "Default")
      (node (ref "JP59") (pin "2") (pinfunction "2_2") (pintype "passive"))
      (node (ref "R17") (pin "1") (pinfunction "1_1") (pintype "passive"))
    )
    (net (code "135") (name "Net-(JP60-Pad2)") (class "Default")
      (node (ref "JP60") (pin "2") (pinfunction "2_2") (pintype "passive"))
      (node (ref "R16") (pin "1") (pinfunction "1_1") (pintype "passive"))
    )
    (net (code "136") (name "Net-(JP61-Pad2)") (class "Default")
      (node (ref "JP61") (pin "2") (pinfunction "2_2") (pintype "passive"))
      (node (ref "R15") (pin "1") (pinfunction "1_1") (pintype "passive"))
    )
    (net (code "137") (name "Net-(JP62-Pad2)") (class "Default")
      (node (ref "JP62") (pin "2") (pinfunction "2_2") (pintype "passive"))
      (node (ref "R14") (pin "1") (pinfunction "1_1") (pintype "passive"))
    )
    (net (code "138") (name "Net-(JP65-Pad1)") (class "Default")
      (node (ref "JP65") (pin "1") (pinfunction "1_1") (pintype "passive"))
      (node (ref "JP65") (pin "2") (pinfunction "2_2") (pintype "passive"))
      (node (ref "R23") (pin "1") (pinfunction "1_1") (pintype "passive"))
    )
    (net (code "139") (name "Net-(JP66-Pad1)") (class "Default")
      (node (ref "JP66") (pin "1") (pinfunction "1_1") (pintype "passive"))
      (node (ref "JP66") (pin "2") (pinfunction "2_2") (pintype "passive"))
      (node (ref "R22") (pin "1") (pinfunction "1_1") (pintype "passive"))
    )
    (net (code "140") (name "Net-(JP68-Pad1)") (class "Default")
      (node (ref "JP68") (pin "1") (pinfunction "1_1") (pintype "passive"))
      (node (ref "JP68") (pin "2") (pinfunction "2_2") (pintype "passive"))
      (node (ref "JP68") (pin "3") (pinfunction "3_3") (pintype "passive"))
      (node (ref "JP68") (pin "4") (pinfunction "4_4") (pintype "passive"))
      (node (ref "JP68") (pin "5") (pinfunction "5_5") (pintype "passive"))
      (node (ref "JP68") (pin "6") (pinfunction "6_6") (pintype "passive"))
      (node (ref "JP68") (pin "7") (pinfunction "7_7") (pintype "passive"))
      (node (ref "JP68") (pin "8") (pinfunction "8_8") (pintype "passive"))
    )
    (net (code "141") (name "Net-(JP69-Pad1)") (class "Default")
      (node (ref "JP69") (pin "1") (pinfunction "1_1") (pintype "passive"))
      (node (ref "JP69") (pin "2") (pinfunction "2_2") (pintype "passive"))
      (node (ref "JP69") (pin "3") (pinfunction "3_3") (pintype "passive"))
      (node (ref "JP69") (pin "4") (pinfunction "4_4") (pintype "passive"))
      (node (ref "JP69") (pin "5") (pinfunction "5_5") (pintype "passive"))
      (node (ref "JP69") (pin "6") (pinfunction "6_6") (pintype "passive"))
      (node (ref "JP69") (pin "7") (pinfunction "7_7") (pintype "passive"))
      (node (ref "JP69") (pin "8") (pinfunction "8_8") (pintype "passive"))
    )
    (net (code "142") (name "Net-(JP72-Pad1)") (class "Default")
      (node (ref "JP72") (pin "1") (pinfunction "1_1") (pintype "passive"))
      (node (ref "LED6") (pin "1") (pinfunction "A_1") (pintype "passive"))
      (node (ref "LED6") (pin "6") (pinfunction "A_6") (pintype "passive"))
    )
    (net (code "143") (name "Net-(JP73-Pad1)") (class "Default")
      (node (ref "JP73") (pin "1") (pinfunction "1_1") (pintype "passive"))
      (node (ref "LED7") (pin "1") (pinfunction "A_1") (pintype "passive"))
      (node (ref "LED7") (pin "6") (pinfunction "A_6") (pintype "passive"))
    )
    (net (code "144") (name "Net-(JP74-Pad1)") (class "Default")
      (node (ref "JP74") (pin "1") (pinfunction "1_1") (pintype "passive"))
      (node (ref "U$1") (pin "PB12_VL") (pinfunction "PB12_VL_PB12_VL") (pintype "bidirectional"))
    )
    (net (code "145") (name "Net-(JP74-Pad2)") (class "Default")
      (node (ref "JP74") (pin "2") (pinfunction "2_2") (pintype "passive"))
      (node (ref "U$1") (pin "PB11_VL") (pinfunction "PB11_VL_PB11_VL") (pintype "bidirectional"))
    )
    (net (code "146") (name "Net-(JP74-Pad3)") (class "Default")
      (node (ref "JP74") (pin "3") (pinfunction "3_3") (pintype "passive"))
      (node (ref "U$1") (pin "PB10_VL") (pinfunction "PB10_VL_PB10_VL") (pintype "bidirectional"))
    )
    (net (code "147") (name "Net-(LCD1-A1+)") (class "Default")
      (node (ref "LCD1") (pin "1") (pinfunction "A1+_1") (pintype "bidirectional"))
      (node (ref "R8") (pin "1") (pinfunction "1_1") (pintype "passive"))
    )
    (net (code "148") (name "Net-(LCD1-A2+)") (class "Default")
      (node (ref "LCD1") (pin "20") (pinfunction "A2+_20") (pintype "bidirectional"))
      (node (ref "R7") (pin "1") (pinfunction "1_1") (pintype "passive"))
    )
    (net (code "149") (name "Net-(LCD1-CAP1N)") (class "Default")
      (node (ref "C2") (pin "1") (pinfunction "1_1") (pintype "passive"))
      (node (ref "LCD1") (pin "21") (pinfunction "CAP1N_21") (pintype "bidirectional"))
    )
    (net (code "150") (name "Net-(LCD1-CAP1P)") (class "Default")
      (node (ref "C2") (pin "2") (pinfunction "2_2") (pintype "passive"))
      (node (ref "LCD1") (pin "22") (pinfunction "CAP1P_22") (pintype "bidirectional"))
    )
    (net (code "151") (name "Net-(LCD1-D0)") (class "Default")
      (node (ref "LCD1") (pin "30") (pinfunction "D5_30") (pintype "bidirectional"))
      (node (ref "LCD1") (pin "31") (pinfunction "D4_31") (pintype "bidirectional"))
      (node (ref "LCD1") (pin "32") (pinfunction "D3_32") (pintype "bidirectional"))
      (node (ref "LCD1") (pin "33") (pinfunction "D2_33") (pintype "bidirectional"))
      (node (ref "LCD1") (pin "34") (pinfunction "D1_34") (pintype "bidirectional"))
      (node (ref "LCD1") (pin "35") (pinfunction "D0_35") (pintype "bidirectional"))
      (node (ref "LCD1") (pin "36") (pinfunction "E_36") (pintype "bidirectional"))
      (node (ref "LCD1") (pin "37") (pinfunction "R/W_37") (pintype "bidirectional"))
      (node (ref "LCD1") (pin "40") (pinfunction "RESET_40") (pintype "bidirectional"))
      (node (ref "R10") (pin "1") (pinfunction "1_1") (pintype "passive"))
    )
    (net (code "152") (name "Net-(LCD1-VOUT)") (class "Default")
      (node (ref "C3") (pin "2") (pinfunction "2_2") (pintype "passive"))
      (node (ref "LCD1") (pin "24") (pinfunction "VOUT_24") (pintype "bidirectional"))
    )
    (net (code "153") (name "Net-(LED1-C)") (class "Default")
      (node (ref "LED1") (pin "K") (pinfunction "C_K") (pintype "passive"))
      (node (ref "R1") (pin "2") (pinfunction "2_2") (pintype "passive"))
    )
    (net (code "154") (name "Net-(LED2-C)") (class "Default")
      (node (ref "LED2") (pin "K") (pinfunction "C_K") (pintype "passive"))
      (node (ref "R2") (pin "2") (pinfunction "2_2") (pintype "passive"))
    )
    (net (code "155") (name "Net-(LED3-C)") (class "Default")
      (node (ref "LED3") (pin "K") (pinfunction "C_K") (pintype "passive"))
      (node (ref "R3") (pin "2") (pinfunction "2_2") (pintype "passive"))
    )
    (net (code "156") (name "Net-(LED4-C)") (class "Default")
      (node (ref "LED4") (pin "K") (pinfunction "C_K") (pintype "passive"))
      (node (ref "R4") (pin "2") (pinfunction "2_2") (pintype "passive"))
    )
    (net (code "157") (name "Net-(LED5-C)") (class "Default")
      (node (ref "LED5") (pin "K") (pinfunction "C_K") (pintype "passive"))
      (node (ref "R6") (pin "1") (pinfunction "1_1") (pintype "passive"))
    )
    (net (code "158") (name "Net-(LED6-A-Pad10)") (class "Default")
      (node (ref "LED6") (pin "10") (pinfunction "A_10") (pintype "passive"))
      (node (ref "LED7") (pin "10") (pinfunction "A_10") (pintype "passive"))
      (node (ref "LED8") (pin "10") (pinfunction "A_10") (pintype "passive"))
      (node (ref "R24") (pin "2") (pinfunction "2_2") (pintype "passive"))
    )
    (net (code "159") (name "Net-(LED6-B)") (class "Default")
      (node (ref "LED6") (pin "9") (pinfunction "B_9") (pintype "passive"))
      (node (ref "LED7") (pin "9") (pinfunction "B_9") (pintype "passive"))
      (node (ref "LED8") (pin "9") (pinfunction "B_9") (pintype "passive"))
      (node (ref "R25") (pin "2") (pinfunction "2_2") (pintype "passive"))
    )
    (net (code "160") (name "Net-(LED6-C)") (class "Default")
      (node (ref "LED6") (pin "8") (pinfunction "C_8") (pintype "passive"))
      (node (ref "LED7") (pin "8") (pinfunction "C_8") (pintype "passive"))
      (node (ref "LED8") (pin "8") (pinfunction "C_8") (pintype "passive"))
      (node (ref "R26") (pin "2") (pinfunction "2_2") (pintype "passive"))
    )
    (net (code "161") (name "Net-(LED6-D)") (class "Default")
      (node (ref "LED6") (pin "5") (pinfunction "D_5") (pintype "passive"))
      (node (ref "LED7") (pin "5") (pinfunction "D_5") (pintype "passive"))
      (node (ref "LED8") (pin "5") (pinfunction "D_5") (pintype "passive"))
      (node (ref "R27") (pin "2") (pinfunction "2_2") (pintype "passive"))
    )
    (net (code "162") (name "Net-(LED6-DP)") (class "Default")
      (node (ref "LED6") (pin "7") (pinfunction "DP_7") (pintype "passive"))
      (node (ref "LED7") (pin "7") (pinfunction "DP_7") (pintype "passive"))
      (node (ref "LED8") (pin "7") (pinfunction "DP_7") (pintype "passive"))
      (node (ref "R31") (pin "2") (pinfunction "2_2") (pintype "passive"))
    )
    (net (code "163") (name "Net-(LED6-E)") (class "Default")
      (node (ref "LED6") (pin "4") (pinfunction "E_4") (pintype "passive"))
      (node (ref "LED7") (pin "4") (pinfunction "E_4") (pintype "passive"))
      (node (ref "LED8") (pin "4") (pinfunction "E_4") (pintype "passive"))
      (node (ref "R28") (pin "2") (pinfunction "2_2") (pintype "passive"))
    )
    (net (code "164") (name "Net-(LED6-F)") (class "Default")
      (node (ref "LED6") (pin "2") (pinfunction "F_2") (pintype "passive"))
      (node (ref "LED7") (pin "2") (pinfunction "F_2") (pintype "passive"))
      (node (ref "LED8") (pin "2") (pinfunction "F_2") (pintype "passive"))
      (node (ref "R29") (pin "2") (pinfunction "2_2") (pintype "passive"))
    )
    (net (code "165") (name "Net-(LED6-G)") (class "Default")
      (node (ref "LED6") (pin "3") (pinfunction "G_3") (pintype "passive"))
      (node (ref "LED7") (pin "3") (pinfunction "G_3") (pintype "passive"))
      (node (ref "LED8") (pin "3") (pinfunction "G_3") (pintype "passive"))
      (node (ref "R30") (pin "2") (pinfunction "2_2") (pintype "passive"))
    )
    (net (code "166") (name "Net-(LED9-C)") (class "Default")
      (node (ref "LED9") (pin "K") (pinfunction "C_K") (pintype "passive"))
      (node (ref "R32") (pin "2") (pinfunction "2_2") (pintype "passive"))
    )
    (net (code "167") (name "Net-(LED10-C)") (class "Default")
      (node (ref "LED10") (pin "K") (pinfunction "C_K") (pintype "passive"))
      (node (ref "R34") (pin "2") (pinfunction "2_2") (pintype "passive"))
    )
    (net (code "168") (name "Net-(LED11-C)") (class "Default")
      (node (ref "LED11") (pin "K") (pinfunction "C_K") (pintype "passive"))
      (node (ref "R33") (pin "2") (pinfunction "2_2") (pintype "passive"))
    )
    (net (code "169") (name "Net-(LED12-C)") (class "Default")
      (node (ref "LED12") (pin "K") (pinfunction "C_K") (pintype "passive"))
      (node (ref "R35") (pin "2") (pinfunction "2_2") (pintype "passive"))
    )
    (net (code "170") (name "Net-(S1-P)") (class "Default")
      (node (ref "JP62") (pin "3") (pinfunction "3_3") (pintype "passive"))
      (node (ref "JP9") (pin "1") (pinfunction "1_1") (pintype "passive"))
      (node (ref "S1") (pin "3") (pinfunction "P_3") (pintype "passive"))
      (node (ref "S1") (pin "4") (pinfunction "P1_4") (pintype "passive"))
    )
    (net (code "171") (name "Net-(S2-P)") (class "Default")
      (node (ref "JP10") (pin "1") (pinfunction "1_1") (pintype "passive"))
      (node (ref "JP61") (pin "3") (pinfunction "3_3") (pintype "passive"))
      (node (ref "S2") (pin "3") (pinfunction "P_3") (pintype "passive"))
      (node (ref "S2") (pin "4") (pinfunction "P1_4") (pintype "passive"))
    )
    (net (code "172") (name "Net-(S3-P)") (class "Default")
      (node (ref "JP11") (pin "1") (pinfunction "1_1") (pintype "passive"))
      (node (ref "JP60") (pin "3") (pinfunction "3_3") (pintype "passive"))
      (node (ref "S3") (pin "3") (pinfunction "P_3") (pintype "passive"))
      (node (ref "S3") (pin "4") (pinfunction "P1_4") (pintype "passive"))
    )
    (net (code "173") (name "Net-(S4-P)") (class "Default")
      (node (ref "JP12") (pin "1") (pinfunction "1_1") (pintype "passive"))
      (node (ref "JP59") (pin "3") (pinfunction "3_3") (pintype "passive"))
      (node (ref "S4") (pin "3") (pinfunction "P_3") (pintype "passive"))
      (node (ref "S4") (pin "4") (pinfunction "P1_4") (pintype "passive"))
    )
    (net (code "174") (name "Net-(SP1-1)") (class "Default")
      (node (ref "SP1") (pin "-") (pinfunction "1_-") (pintype "passive"))
      (node (ref "T1") (pin "3") (pinfunction "C_3") (pintype "passive"))
    )
    (net (code "175") (name "Net-(SW1B-2)") (class "Default")
      (node (ref "JP13") (pin "1") (pinfunction "1_1") (pintype "passive"))
      (node (ref "R20") (pin "2") (pinfunction "2_2") (pintype "passive"))
      (node (ref "SW1") (pin "E") (pinfunction "2_E") (pintype "passive"))
    )
    (net (code "176") (name "Net-(T1-B)") (class "Default")
      (node (ref "R21") (pin "1") (pinfunction "1_1") (pintype "passive"))
      (node (ref "T1") (pin "2") (pinfunction "B_2") (pintype "passive"))
    )
    (net (code "177") (name "Net-(U$1-EXT_VBAT_VL)") (class "Default")
      (node (ref "JP16") (pin "22") (pinfunction "22_22") (pintype "passive"))
      (node (ref "U$1") (pin "VBAT_EXT_VL") (pinfunction "EXT_VBAT_VL_VBAT_EXT_VL") (pintype "bidirectional"))
    )
    (net (code "178") (name "Net-(U$1-RESET#_VL)") (class "Default")
      (node (ref "JP16") (pin "16") (pinfunction "16_16") (pintype "passive"))
      (node (ref "U$1") (pin "RESET_VL") (pinfunction "RESET#_VL_RESET_VL") (pintype "bidirectional"))
    )
    (net (code "179") (name "Net-(U$2-CTS)") (class "Default")
      (node (ref "JP38") (pin "1") (pinfunction "1_1") (pintype "passive"))
      (node (ref "U$2") (pin "5") (pinfunction "CTS_5") (pintype "bidirectional"))
    )
    (net (code "180") (name "Net-(U$2-DCD)") (class "Default")
      (node (ref "JP36") (pin "1") (pinfunction "1_1") (pintype "passive"))
      (node (ref "U$2") (pin "1") (pinfunction "DCD_1") (pintype "bidirectional"))
    )
    (net (code "181") (name "Net-(U$2-DSR)") (class "Default")
      (node (ref "JP36") (pin "3") (pinfunction "3_3") (pintype "passive"))
      (node (ref "U$2") (pin "3") (pinfunction "DSR_3") (pintype "bidirectional"))
    )
    (net (code "182") (name "Net-(U$2-DTR)") (class "Default")
      (node (ref "JP36") (pin "2") (pinfunction "2_2") (pintype "passive"))
      (node (ref "U$2") (pin "2") (pinfunction "DTR_2") (pintype "bidirectional"))
    )
    (net (code "183") (name "Net-(U$2-GND)") (class "Default")
      (node (ref "JP38") (pin "2") (pinfunction "2_2") (pintype "passive"))
      (node (ref "U$2") (pin "6") (pinfunction "GND_6") (pintype "bidirectional"))
    )
    (net (code "184") (name "Net-(U$2-RI)") (class "Default")
      (node (ref "JP37") (pin "3") (pinfunction "3_3") (pintype "passive"))
      (node (ref "U$2") (pin "13") (pinfunction "RI_13") (pintype "bidirectional"))
    )
    (net (code "185") (name "Net-(U$2-RST_N)") (class "Default")
      (node (ref "JP37") (pin "2") (pinfunction "2_2") (pintype "passive"))
      (node (ref "U$2") (pin "12") (pinfunction "RST_N_12") (pintype "bidirectional"))
    )
    (net (code "186") (name "Net-(U$2-RTS)") (class "Default")
      (node (ref "JP36") (pin "4") (pinfunction "4_4") (pintype "passive"))
      (node (ref "U$2") (pin "4") (pinfunction "RTS_4") (pintype "bidirectional"))
    )
    (net (code "187") (name "Net-(U$2-RX)") (class "Default")
      (node (ref "JP38") (pin "5") (pinfunction "5_5") (pintype "passive"))
      (node (ref "U$2") (pin "9") (pinfunction "RX_9") (pintype "bidirectional"))
    )
    (net (code "188") (name "Net-(U$2-SUSPEND)") (class "Default")
      (node (ref "JP38") (pin "6") (pinfunction "6_6") (pintype "passive"))
      (node (ref "U$2") (pin "10") (pinfunction "SUSPEND_10") (pintype "bidirectional"))
    )
    (net (code "189") (name "Net-(U$2-SUSPEND_N)") (class "Default")
      (node (ref "JP37") (pin "1") (pinfunction "1_1") (pintype "passive"))
      (node (ref "U$2") (pin "11") (pinfunction "SUSPEND_N_11") (pintype "bidirectional"))
    )
    (net (code "190") (name "Net-(U$2-TX)") (class "Default")
      (node (ref "JP38") (pin "3") (pinfunction "3_3") (pintype "passive"))
      (node (ref "U$2") (pin "7") (pinfunction "TX_7") (pintype "bidirectional"))
    )
    (net (code "191") (name "Net-(U$2-VBUS)") (class "Default")
      (node (ref "JP38") (pin "4") (pinfunction "4_4") (pintype "passive"))
      (node (ref "U$2") (pin "8") (pinfunction "VBUS_8") (pintype "bidirectional"))
    )
    (net (code "192") (name "Net-(U$2-VDD)") (class "Default")
      (node (ref "JP37") (pin "4") (pinfunction "4_4") (pintype "passive"))
      (node (ref "U$2") (pin "14") (pinfunction "VDD_14") (pintype "bidirectional"))
    )
    (net (code "193") (name "Net-(U$4-COMM(2))") (class "Default")
      (node (ref "3V3") (pin "VIN") (pinfunction "VIN_VIN") (pintype "bidirectional"))
      (node (ref "5V") (pin "VIN") (pinfunction "VIN_VIN") (pintype "bidirectional"))
      (node (ref "U$4") (pin "2") (pinfunction "COMM(2)_2") (pintype "bidirectional"))
    )
    (net (code "194") (name "Net-(U$5-AUD)") (class "Default")
      (node (ref "JP30") (pin "3") (pinfunction "3_3") (pintype "passive"))
      (node (ref "U$5") (pin "1") (pinfunction "AUD_1") (pintype "bidirectional"))
    )
    (net (code "195") (name "Net-(U$5-GND)") (class "Default")
      (node (ref "JP30") (pin "2") (pinfunction "2_2") (pintype "passive"))
      (node (ref "U$5") (pin "2") (pinfunction "GND_2") (pintype "bidirectional"))
    )
    (net (code "196") (name "Net-(U$5-VCC)") (class "Default")
      (node (ref "JP30") (pin "1") (pinfunction "1_1") (pintype "passive"))
      (node (ref "U$5") (pin "3") (pinfunction "VCC_3") (pintype "bidirectional"))
    )
    (net (code "197") (name "Net-(U$6-1)") (class "Default")
      (node (ref "JP43") (pin "1") (pinfunction "1_1") (pintype "passive"))
      (node (ref "U$6") (pin "2") (pinfunction "1_2") (pintype "bidirectional"))
    )
    (net (code "198") (name "Net-(U$6-2)") (class "Default")
      (node (ref "JP43") (pin "2") (pinfunction "2_2") (pintype "passive"))
      (node (ref "U$6") (pin "1") (pinfunction "2_1") (pintype "bidirectional"))
    )
    (net (code "199") (name "Net-(U$7-2)") (class "Default")
      (node (ref "U$4") (pin "3") (pinfunction "3_3") (pintype "bidirectional"))
      (node (ref "U$7") (pin "1") (pinfunction "2_1") (pintype "bidirectional"))
    )
    (net (code "200") (name "Net-(U$9-GND)") (class "Default")
      (node (ref "JP33") (pin "3") (pinfunction "3_3") (pintype "passive"))
      (node (ref "U$9") (pin "3") (pinfunction "GND_3") (pintype "bidirectional"))
    )
    (net (code "201") (name "Net-(U$9-IN+)") (class "Default")
      (node (ref "JP31") (pin "1") (pinfunction "1_1") (pintype "passive"))
      (node (ref "U$9") (pin "6") (pinfunction "IN+_6") (pintype "bidirectional"))
    )
    (net (code "202") (name "Net-(U$9-IN-)") (class "Default")
      (node (ref "JP31") (pin "2") (pinfunction "2_2") (pintype "passive"))
      (node (ref "U$9") (pin "7") (pinfunction "IN-_7") (pintype "bidirectional"))
    )
    (net (code "203") (name "Net-(U$9-OUT+)") (class "Default")
      (node (ref "JP32") (pin "2") (pinfunction "2_2") (pintype "passive"))
      (node (ref "U$9") (pin "1") (pinfunction "OUT+_1") (pintype "bidirectional"))
    )
    (net (code "204") (name "Net-(U$9-OUT-)") (class "Default")
      (node (ref "JP32") (pin "1") (pinfunction "1_1") (pintype "passive"))
      (node (ref "U$9") (pin "2") (pinfunction "OUT-_2") (pintype "bidirectional"))
    )
    (net (code "205") (name "Net-(U$9-PWR)") (class "Default")
      (node (ref "JP33") (pin "2") (pinfunction "2_2") (pintype "passive"))
      (node (ref "U$9") (pin "4") (pinfunction "PWR_4") (pintype "bidirectional"))
    )
    (net (code "206") (name "Net-(U$9-SDN)") (class "Default")
      (node (ref "JP33") (pin "1") (pinfunction "1_1") (pintype "passive"))
      (node (ref "U$9") (pin "5") (pinfunction "SDN_5") (pintype "bidirectional"))
    )
    (net (code "207") (name "Net-(U$9-VOL+)") (class "Default")
      (node (ref "JP34") (pin "3") (pinfunction "3_3") (pintype "passive"))
      (node (ref "U$9") (pin "10") (pinfunction "VOL+_10") (pintype "bidirectional"))
    )
    (net (code "208") (name "Net-(U$9-VOL-)") (class "Default")
      (node (ref "JP34") (pin "1") (pinfunction "1_1") (pintype "passive"))
      (node (ref "U$9") (pin "8") (pinfunction "VOL-_8") (pintype "bidirectional"))
    )
    (net (code "209") (name "Net-(U$9-VOL->)") (class "Default")
      (node (ref "JP34") (pin "2") (pinfunction "2_2") (pintype "passive"))
      (node (ref "U$9") (pin "9") (pinfunction "VOL->_9") (pintype "bidirectional"))
    )
    (net (code "210") (name "Net-(U$10-CLK)") (class "Default")
      (node (ref "JP35") (pin "4") (pinfunction "4_4") (pintype "passive"))
      (node (ref "U$10") (pin "4") (pinfunction "CLK_4") (pintype "bidirectional"))
    )
    (net (code "211") (name "Net-(U$10-GND)") (class "Default")
      (node (ref "JP35") (pin "7") (pinfunction "7_7") (pintype "passive"))
      (node (ref "U$10") (pin "1") (pinfunction "GND_1") (pintype "bidirectional"))
    )
    (net (code "212") (name "Net-(U$10-MISO)") (class "Default")
      (node (ref "JP35") (pin "3") (pinfunction "3_3") (pintype "passive"))
      (node (ref "U$10") (pin "5") (pinfunction "MISO_5") (pintype "bidirectional"))
    )
    (net (code "213") (name "Net-(U$10-MOSI)") (class "Default")
      (node (ref "JP35") (pin "2") (pinfunction "2_2") (pintype "passive"))
      (node (ref "U$10") (pin "6") (pinfunction "MOSI_6") (pintype "bidirectional"))
    )
    (net (code "214") (name "Net-(U$10-SQW)") (class "Default")
      (node (ref "JP35") (pin "5") (pinfunction "5_5") (pintype "passive"))
      (node (ref "U$10") (pin "3") (pinfunction "SQW_3") (pintype "bidirectional"))
    )
    (net (code "215") (name "Net-(U$10-SS)") (class "Default")
      (node (ref "JP35") (pin "1") (pinfunction "1_1") (pintype "passive"))
      (node (ref "U$10") (pin "7") (pinfunction "SS_7") (pintype "bidirectional"))
    )
    (net (code "216") (name "Net-(U$10-VCC)") (class "Default")
      (node (ref "JP35") (pin "6") (pinfunction "6_6") (pintype "passive"))
      (node (ref "U$10") (pin "2") (pinfunction "VCC_2") (pintype "bidirectional"))
    )
    (net (code "217") (name "Net-(U$12-CD)") (class "Default")
      (node (ref "JP39") (pin "1") (pinfunction "1_1") (pintype "passive"))
      (node (ref "U$12") (pin "7") (pinfunction "CD_7") (pintype "bidirectional"))
    )
    (net (code "218") (name "Net-(U$12-CS)") (class "Default")
      (node (ref "JP39") (pin "7") (pinfunction "7_7") (pintype "passive"))
      (node (ref "U$12") (pin "1") (pinfunction "CS_1") (pintype "bidirectional"))
    )
    (net (code "219") (name "Net-(U$12-DI)") (class "Default")
      (node (ref "JP39") (pin "6") (pinfunction "6_6") (pintype "passive"))
      (node (ref "U$12") (pin "2") (pinfunction "DI_2") (pintype "bidirectional"))
    )
    (net (code "220") (name "Net-(U$12-DO)") (class "Default")
      (node (ref "JP39") (pin "2") (pinfunction "2_2") (pintype "passive"))
      (node (ref "U$12") (pin "6") (pinfunction "DO_6") (pintype "bidirectional"))
    )
    (net (code "221") (name "Net-(U$12-GND)") (class "Default")
      (node (ref "JP39") (pin "3") (pinfunction "3_3") (pintype "passive"))
      (node (ref "U$12") (pin "5") (pinfunction "GND_5") (pintype "bidirectional"))
    )
    (net (code "222") (name "Net-(U$12-SCK)") (class "Default")
      (node (ref "JP39") (pin "4") (pinfunction "4_4") (pintype "passive"))
      (node (ref "U$12") (pin "4") (pinfunction "SCK_4") (pintype "bidirectional"))
    )
    (net (code "223") (name "Net-(U$12-VCC)") (class "Default")
      (node (ref "JP39") (pin "5") (pinfunction "5_5") (pintype "passive"))
      (node (ref "U$12") (pin "3") (pinfunction "VCC_3") (pintype "bidirectional"))
    )
    (net (code "224") (name "Net-(U$17-A)") (class "Default")
      (node (ref "JP55") (pin "1") (pinfunction "1_1") (pintype "passive"))
      (node (ref "U$17") (pin "1") (pinfunction "A_1") (pintype "bidirectional"))
    )
    (net (code "225") (name "Net-(U$17-B)") (class "Default")
      (node (ref "JP53") (pin "1") (pinfunction "1_1") (pintype "passive"))
      (node (ref "U$17") (pin "3") (pinfunction "B_3") (pintype "bidirectional"))
    )
    (net (code "226") (name "Net-(U$17-W)") (class "Default")
      (node (ref "JP54") (pin "1") (pinfunction "1_1") (pintype "passive"))
      (node (ref "U$17") (pin "2") (pinfunction "W_2") (pintype "bidirectional"))
    )
    (net (code "227") (name "PWM_MO_1") (class "Default")
      (node (ref "IC2") (pin "1") (pinfunction "1-2EN_1") (pintype "input"))
      (node (ref "JP57") (pin "1") (pinfunction "1_1") (pintype "passive"))
    )
    (net (code "228") (name "PWM_MO_2") (class "Default")
      (node (ref "IC2") (pin "9") (pinfunction "3-4EN_9") (pintype "input"))
      (node (ref "JP58") (pin "2") (pinfunction "2_2") (pintype "passive"))
    )
    (net (code "229") (name "RS_DOG") (class "Default")
      (node (ref "JP1") (pin "2") (pinfunction "2_2") (pintype "passive"))
      (node (ref "LCD1") (pin "39") (pinfunction "RS_39") (pintype "bidirectional"))
      (node (ref "R9") (pin "1") (pinfunction "1_1") (pintype "passive"))
    )
    (net (code "230") (name "SI_DOG") (class "Default")
      (node (ref "JP1") (pin "4") (pinfunction "4_4") (pintype "passive"))
      (node (ref "LCD1") (pin "28") (pinfunction "D7_28") (pintype "bidirectional"))
      (node (ref "R12") (pin "1") (pinfunction "1_1") (pintype "passive"))
    )
    (net (code "231") (name "UEXT_3V3") (class "Default")
      (node (ref "JP20") (pin "1") (pinfunction "1_1") (pintype "passive"))
      (node (ref "JP63") (pin "1") (pinfunction "1_1") (pintype "passive"))
      (node (ref "SV2") (pin "1") (pinfunction "1_1") (pintype "passive"))
    )
    (net (code "232") (name "UEXT_GND") (class "Default")
      (node (ref "JP20") (pin "2") (pinfunction "2_2") (pintype "passive"))
      (node (ref "JP63") (pin "2") (pinfunction "2_2") (pintype "passive"))
      (node (ref "SV2") (pin "2") (pinfunction "2_2") (pintype "passive"))
    )
    (net (code "233") (name "UEXT_MISO") (class "Default")
      (node (ref "JP20") (pin "7") (pinfunction "7_7") (pintype "passive"))
      (node (ref "JP63") (pin "7") (pinfunction "7_7") (pintype "passive"))
      (node (ref "SV2") (pin "7") (pinfunction "7_7") (pintype "passive"))
    )
    (net (code "234") (name "UEXT_MOSI") (class "Default")
      (node (ref "JP20") (pin "8") (pinfunction "8_8") (pintype "passive"))
      (node (ref "JP63") (pin "8") (pinfunction "8_8") (pintype "passive"))
      (node (ref "SV2") (pin "8") (pinfunction "8_8") (pintype "passive"))
    )
    (net (code "235") (name "UEXT_RXD") (class "Default")
      (node (ref "JP20") (pin "4") (pinfunction "4_4") (pintype "passive"))
      (node (ref "JP63") (pin "4") (pinfunction "4_4") (pintype "passive"))
      (node (ref "SV2") (pin "4") (pinfunction "4_4") (pintype "passive"))
    )
    (net (code "236") (name "UEXT_SCK") (class "Default")
      (node (ref "JP20") (pin "9") (pinfunction "9_9") (pintype "passive"))
      (node (ref "JP63") (pin "9") (pinfunction "9_9") (pintype "passive"))
      (node (ref "SV2") (pin "9") (pinfunction "9_9") (pintype "passive"))
    )
    (net (code "237") (name "UEXT_SCL") (class "Default")
      (node (ref "JP20") (pin "5") (pinfunction "5_5") (pintype "passive"))
      (node (ref "JP63") (pin "5") (pinfunction "5_5") (pintype "passive"))
      (node (ref "SV2") (pin "5") (pinfunction "5_5") (pintype "passive"))
    )
    (net (code "238") (name "UEXT_SDA") (class "Default")
      (node (ref "JP20") (pin "6") (pinfunction "6_6") (pintype "passive"))
      (node (ref "JP63") (pin "6") (pinfunction "6_6") (pintype "passive"))
      (node (ref "SV2") (pin "6") (pinfunction "6_6") (pintype "passive"))
    )
    (net (code "239") (name "UEXT_SSEL") (class "Default")
      (node (ref "JP20") (pin "10") (pinfunction "10_10") (pintype "passive"))
      (node (ref "JP63") (pin "10") (pinfunction "10_10") (pintype "passive"))
      (node (ref "SV2") (pin "10") (pinfunction "10_10") (pintype "passive"))
    )
    (net (code "240") (name "UEXT_TXD") (class "Default")
      (node (ref "JP20") (pin "3") (pinfunction "3_3") (pintype "passive"))
      (node (ref "JP63") (pin "3") (pinfunction "3_3") (pintype "passive"))
      (node (ref "SV2") (pin "3") (pinfunction "3_3") (pintype "passive"))
    )
    (net (code "241") (name "V3V_DOG") (class "Default")
      (node (ref "C3") (pin "1") (pinfunction "1_1") (pintype "passive"))
      (node (ref "JP1") (pin "5") (pinfunction "5_5") (pintype "passive"))
      (node (ref "LCD1") (pin "25") (pinfunction "VIN_25") (pintype "bidirectional"))
      (node (ref "LCD1") (pin "26") (pinfunction "VDD_26") (pintype "bidirectional"))
      (node (ref "R10") (pin "2") (pinfunction "2_2") (pintype "passive"))
      (node (ref "R7") (pin "2") (pinfunction "2_2") (pintype "passive"))
      (node (ref "R8") (pin "2") (pinfunction "2_2") (pintype "passive"))
    )
    (net (code "242") (name "unconnected-(3V3-PadSHDN_N)") (class "Default")
      (node (ref "3V3") (pin "SHDN_N") (pinfunction "SHDN_N_SHDN_N") (pintype "bidirectional"))
    )
    (net (code "243") (name "unconnected-(5V-PadSHDN_N)") (class "Default")
      (node (ref "5V") (pin "SHDN_N") (pinfunction "SHDN_N_SHDN_N") (pintype "bidirectional"))
    )
    (net (code "244") (name "unconnected-(JP4-Pad3)") (class "Default")
      (node (ref "JP4") (pin "3") (pinfunction "3_3") (pintype "passive"))
    )
    (net (code "245") (name "unconnected-(JP59-Pad1)") (class "Default")
      (node (ref "JP59") (pin "1") (pinfunction "1_1") (pintype "passive"))
    )
    (net (code "246") (name "unconnected-(JP60-Pad1)") (class "Default")
      (node (ref "JP60") (pin "1") (pinfunction "1_1") (pintype "passive"))
    )
    (net (code "247") (name "unconnected-(JP61-Pad1)") (class "Default")
      (node (ref "JP61") (pin "1") (pinfunction "1_1") (pintype "passive"))
    )
    (net (code "248") (name "unconnected-(JP62-Pad1)") (class "Default")
      (node (ref "JP62") (pin "1") (pinfunction "1_1") (pintype "passive"))
    )
    (net (code "249") (name "unconnected-(X1-Pad3)") (class "Default")
      (node (ref "X1") (pin "3") (pinfunction "3_3") (pintype "passive"))
    )
  )
)
